# plaits_v50.net
KiCad netlist of a schematic drawn in EAGLE
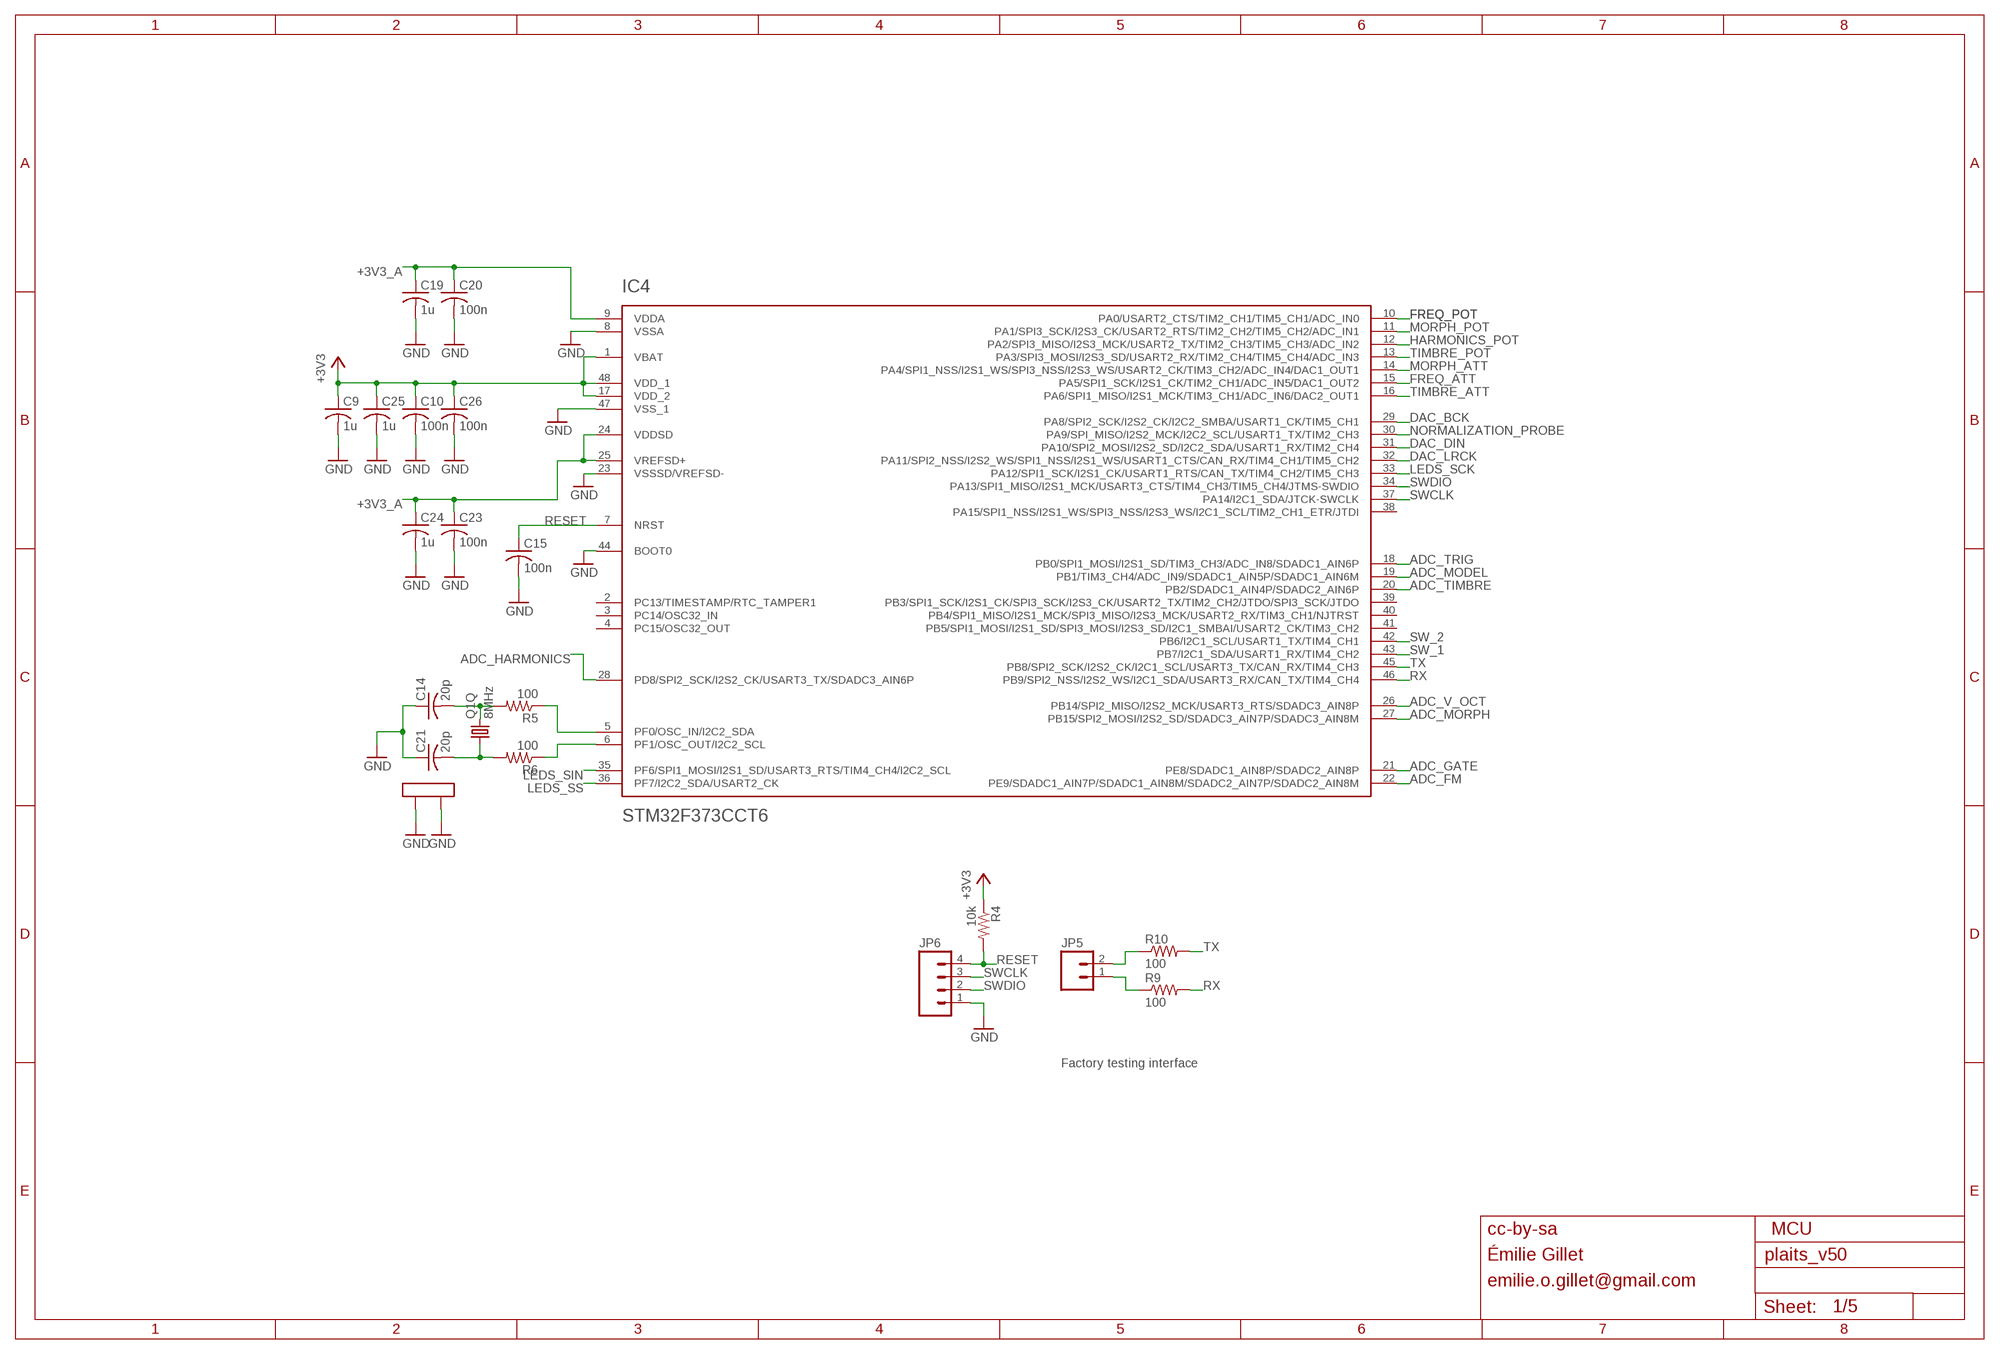
[diagram p0: schematic, sheet 1]
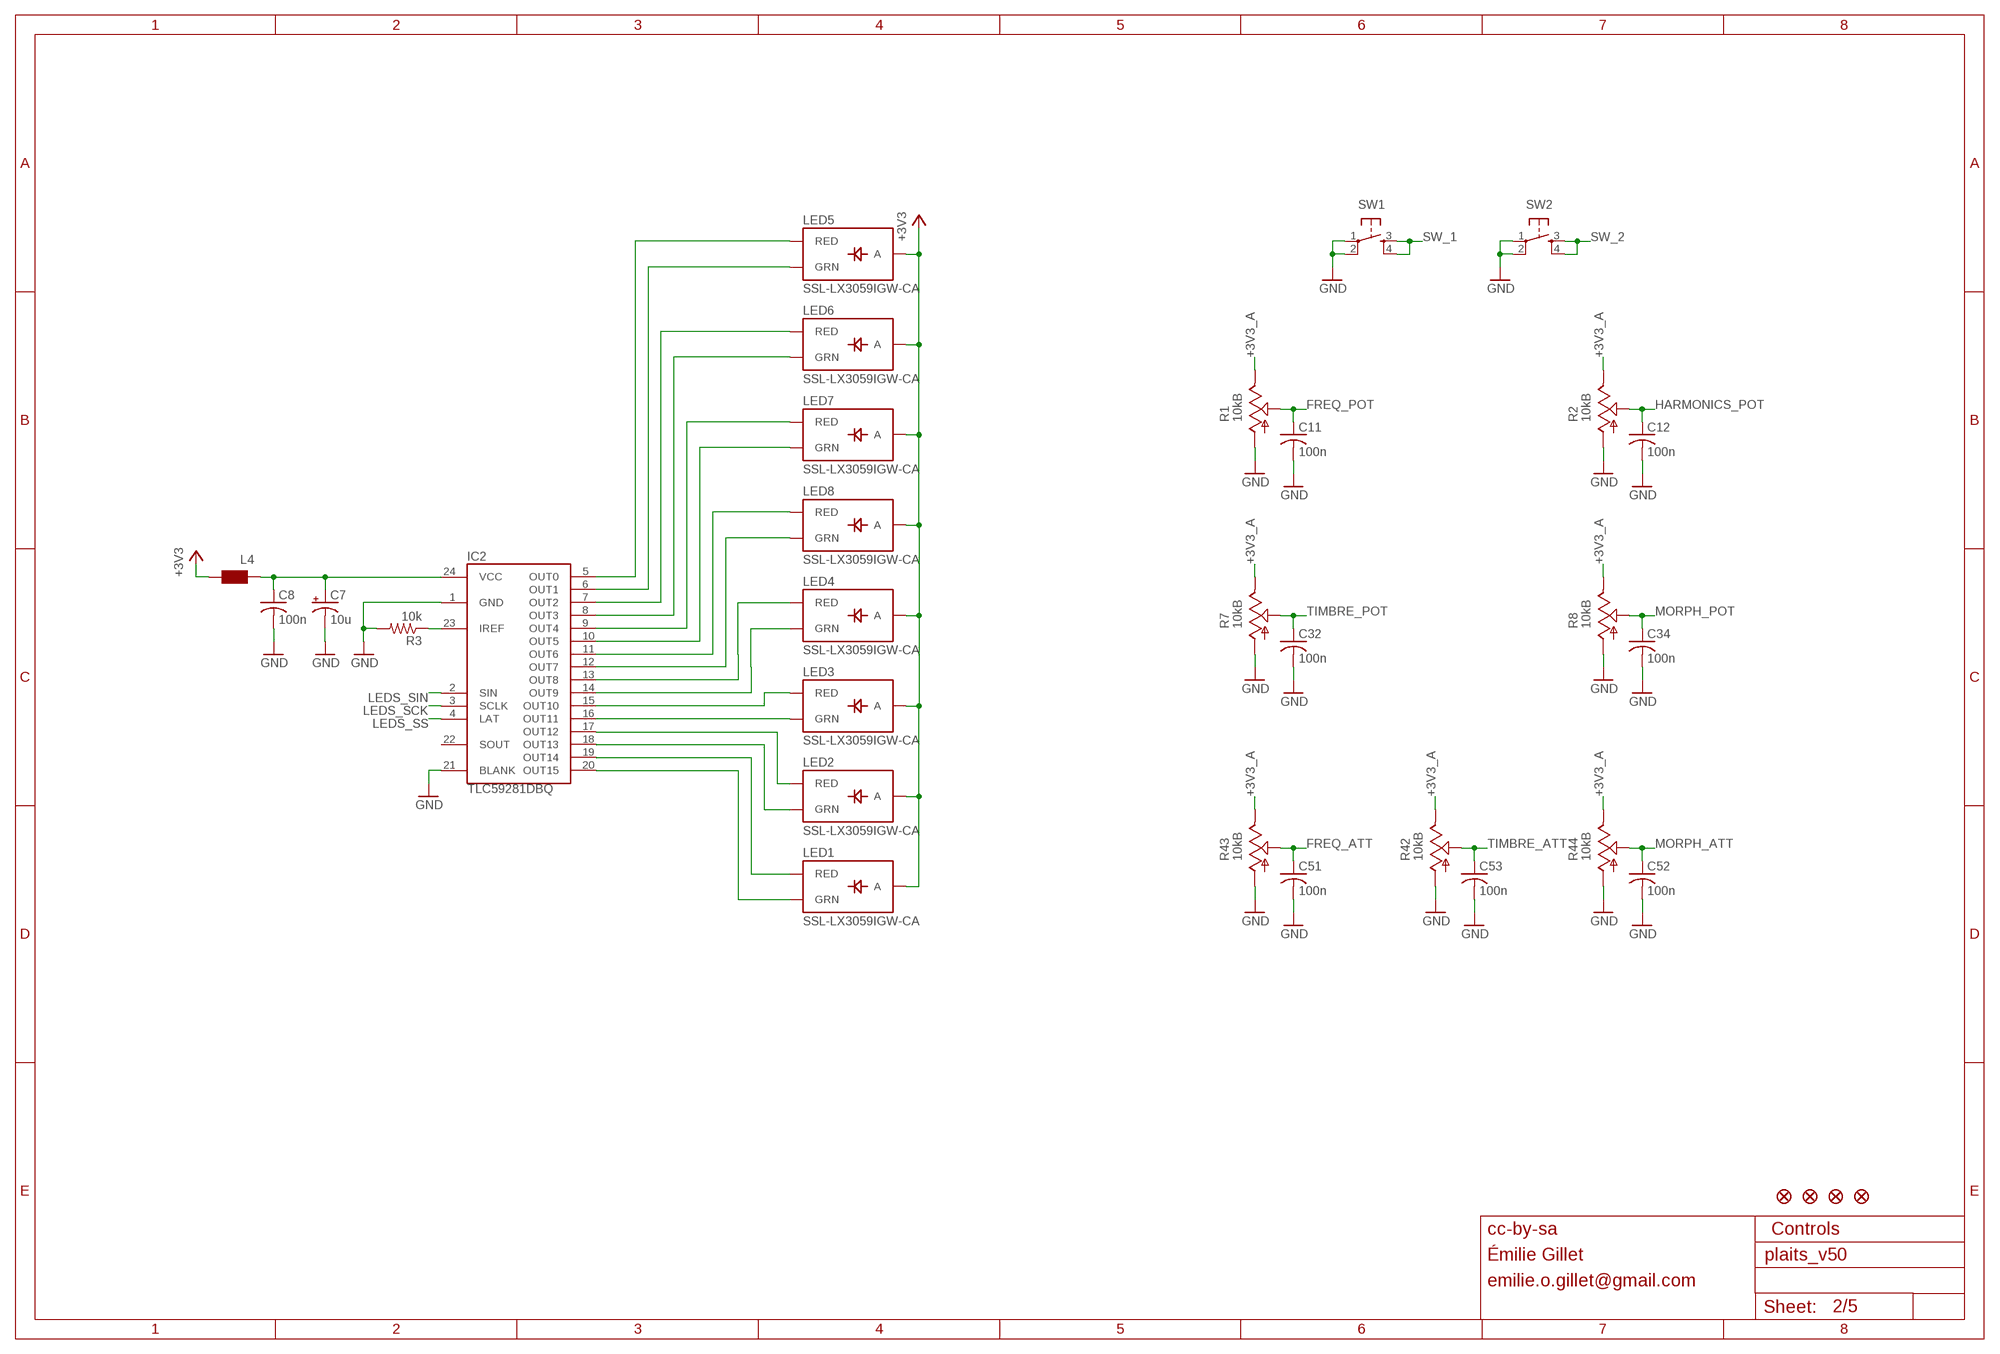
[diagram p1: schematic, sheet 2]
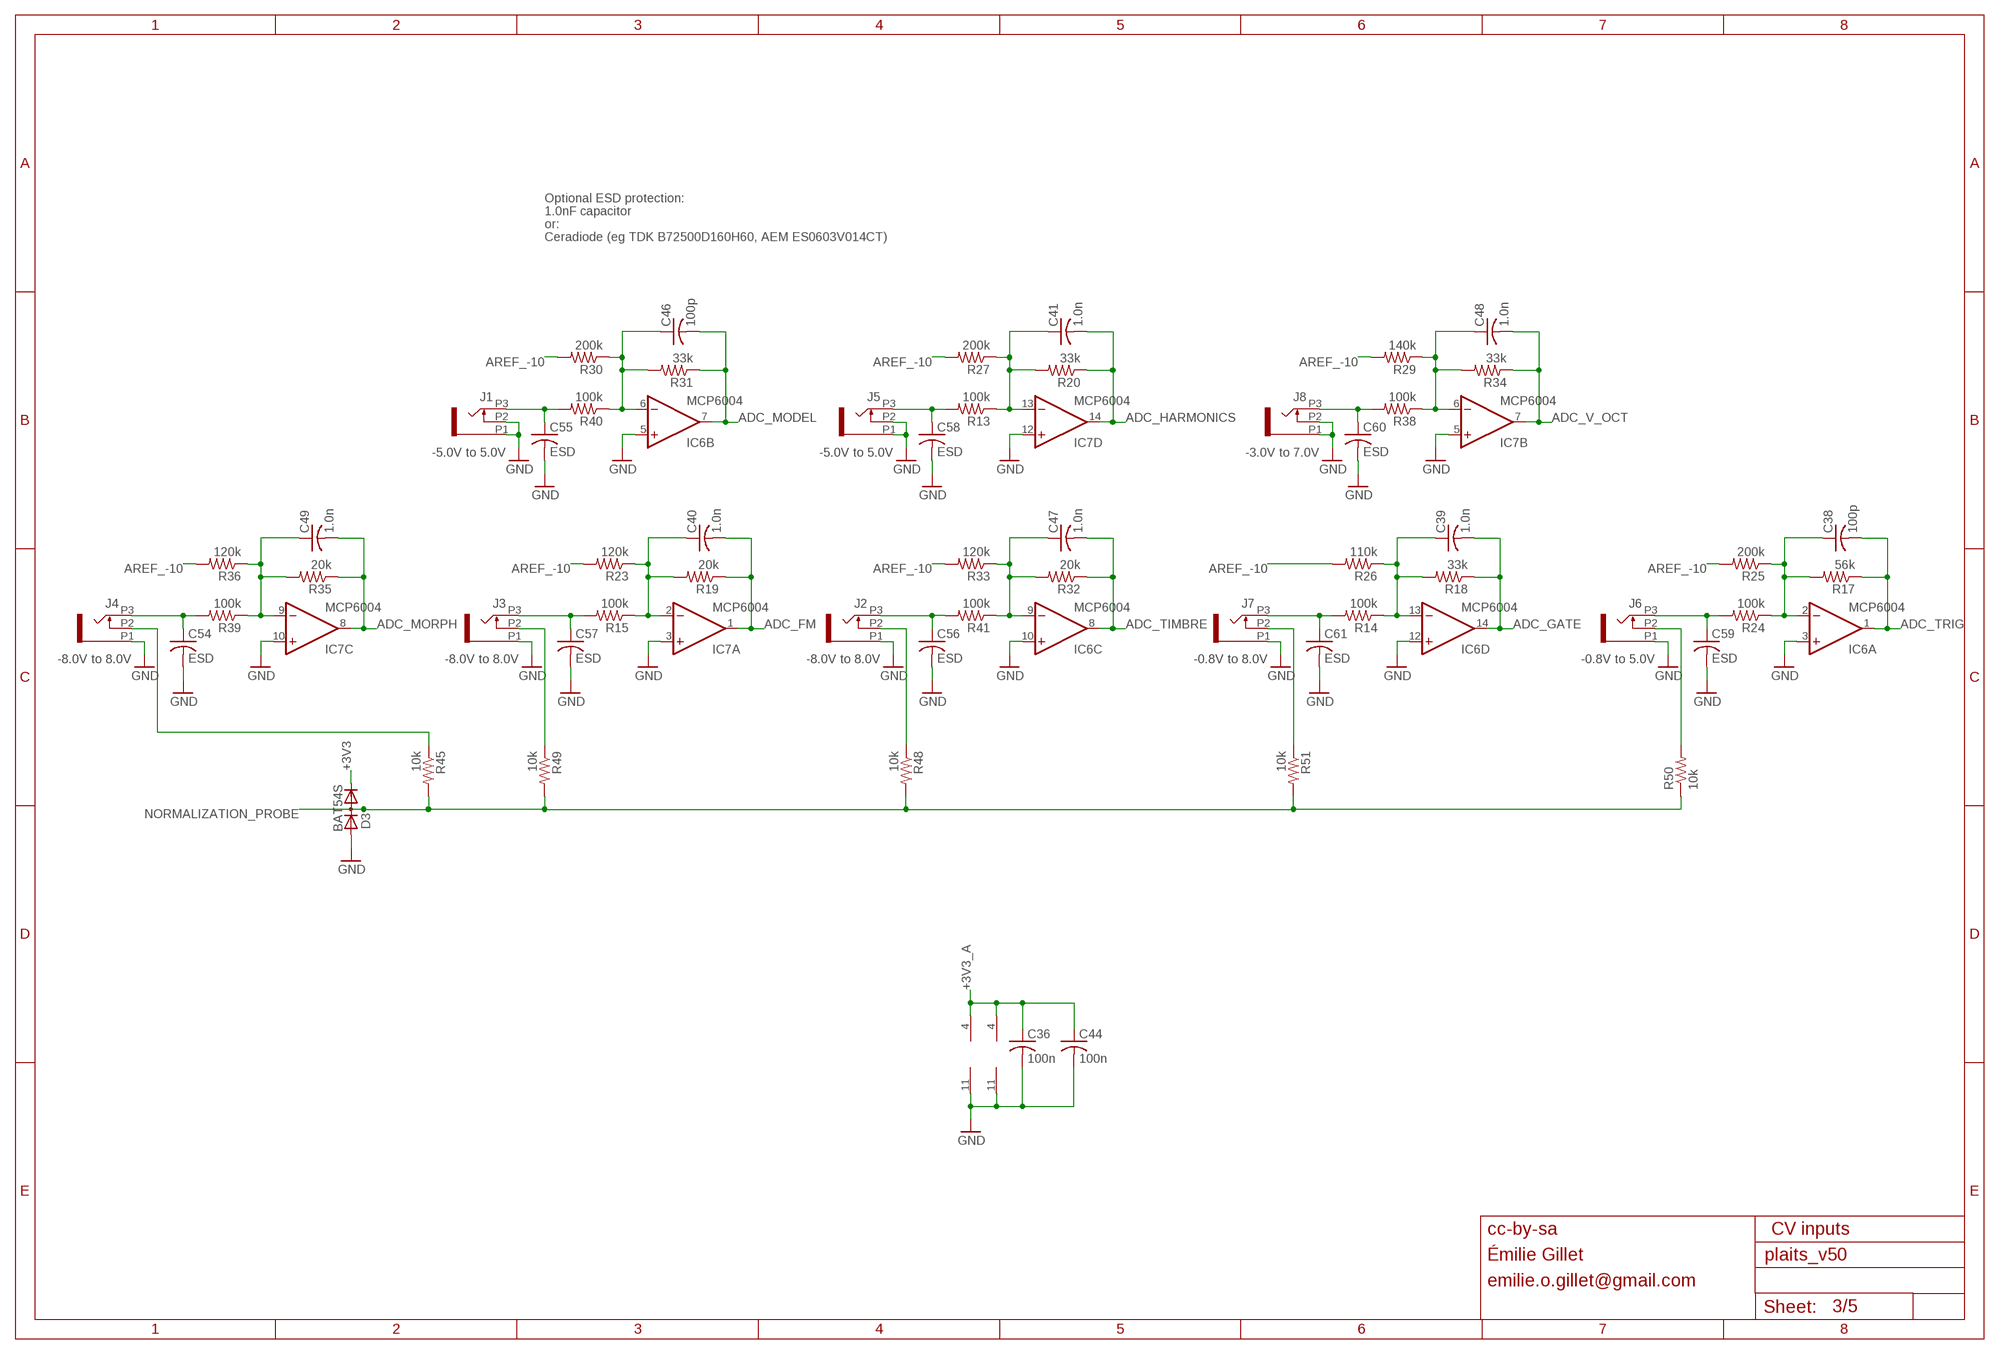
[diagram p2: schematic, sheet 3]
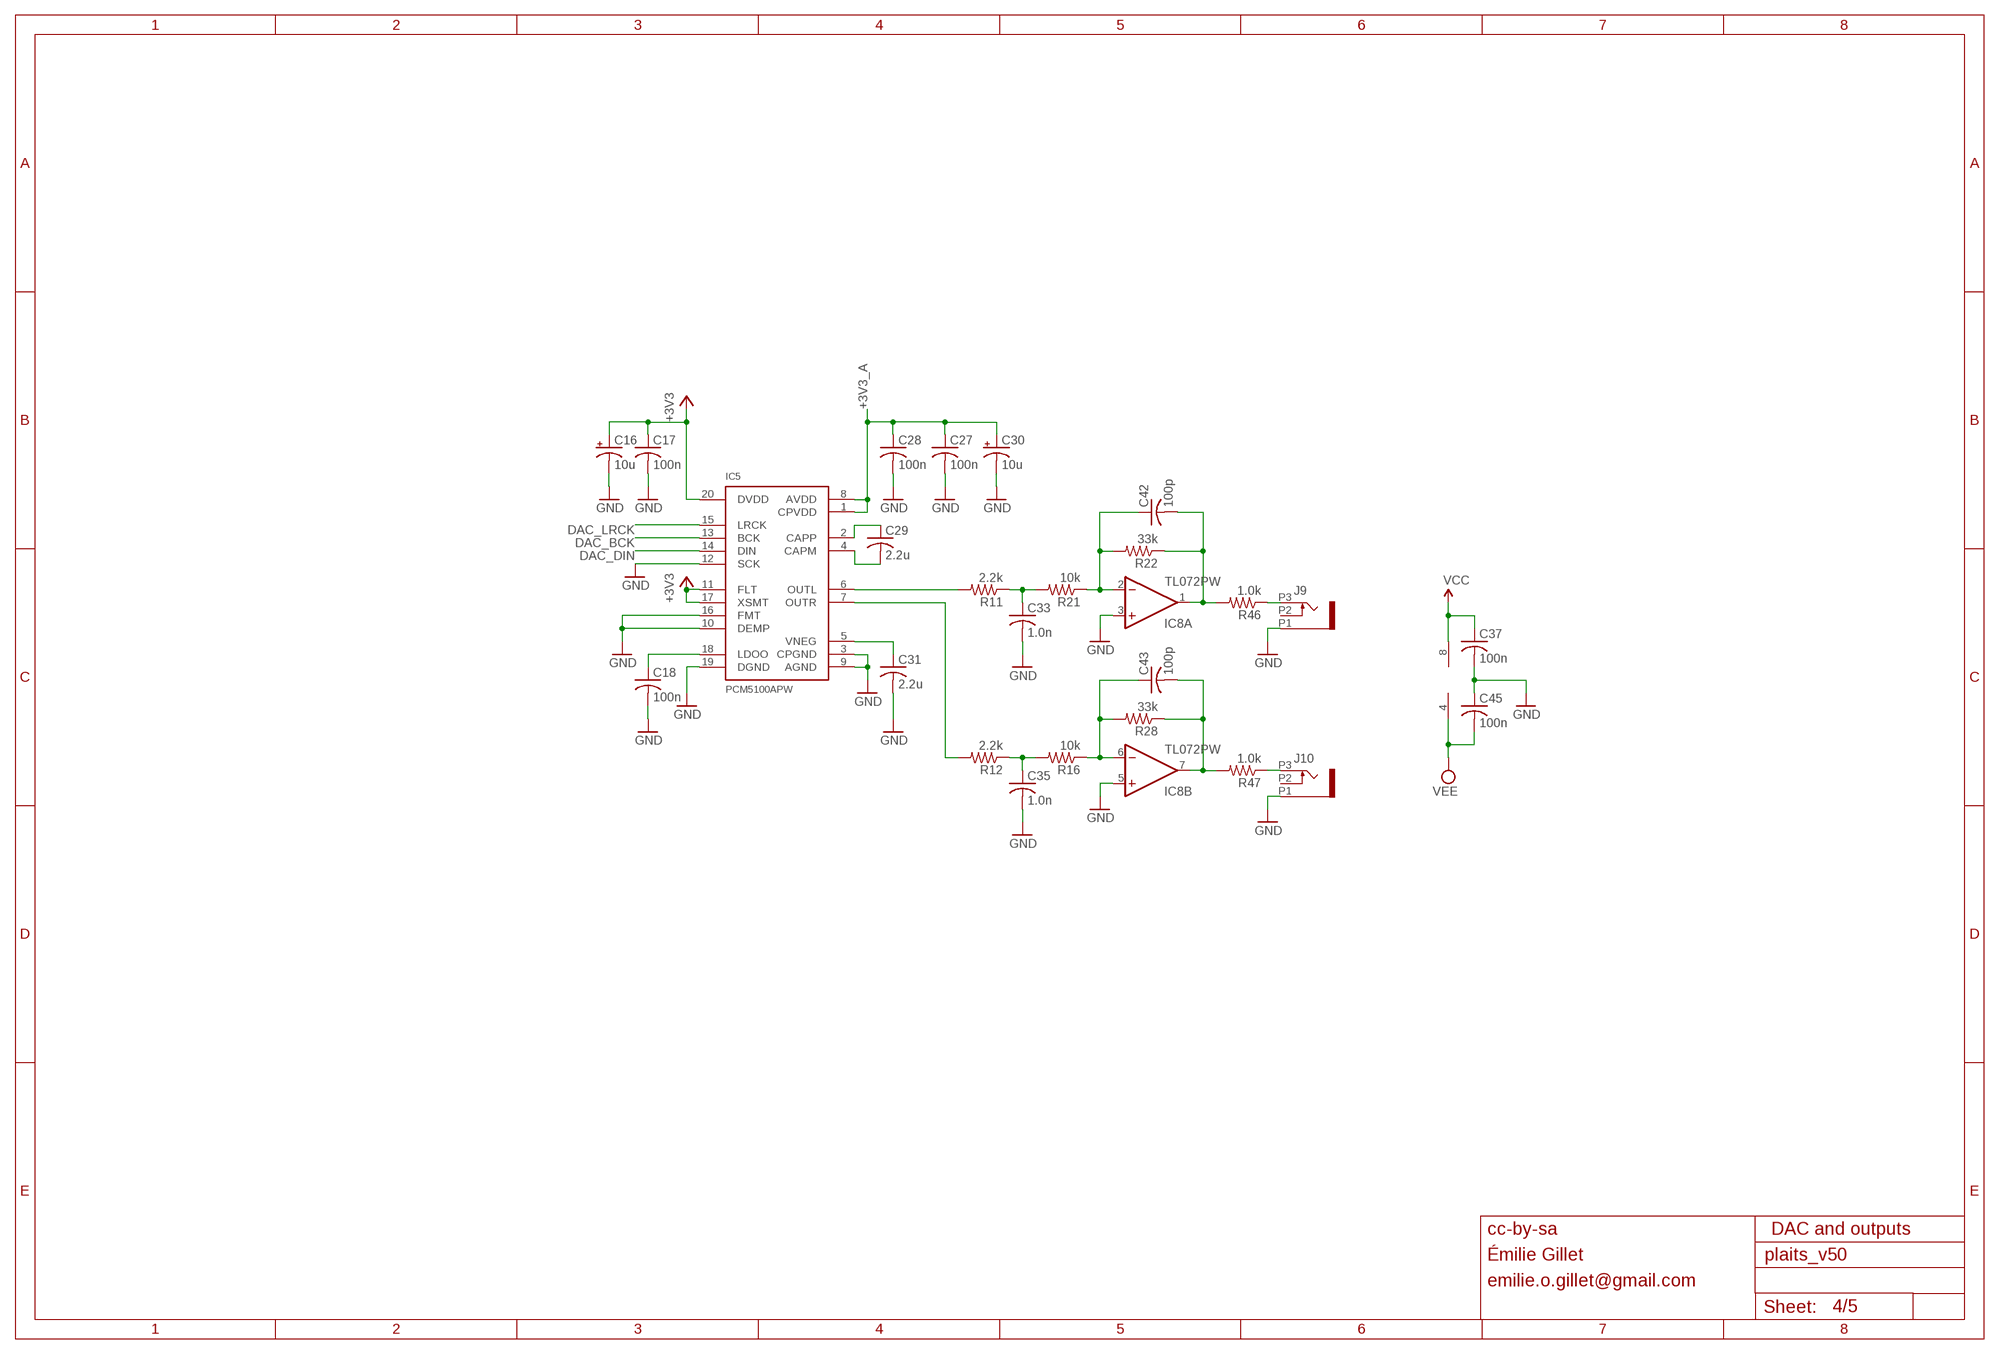
[diagram p3: schematic, sheet 4]
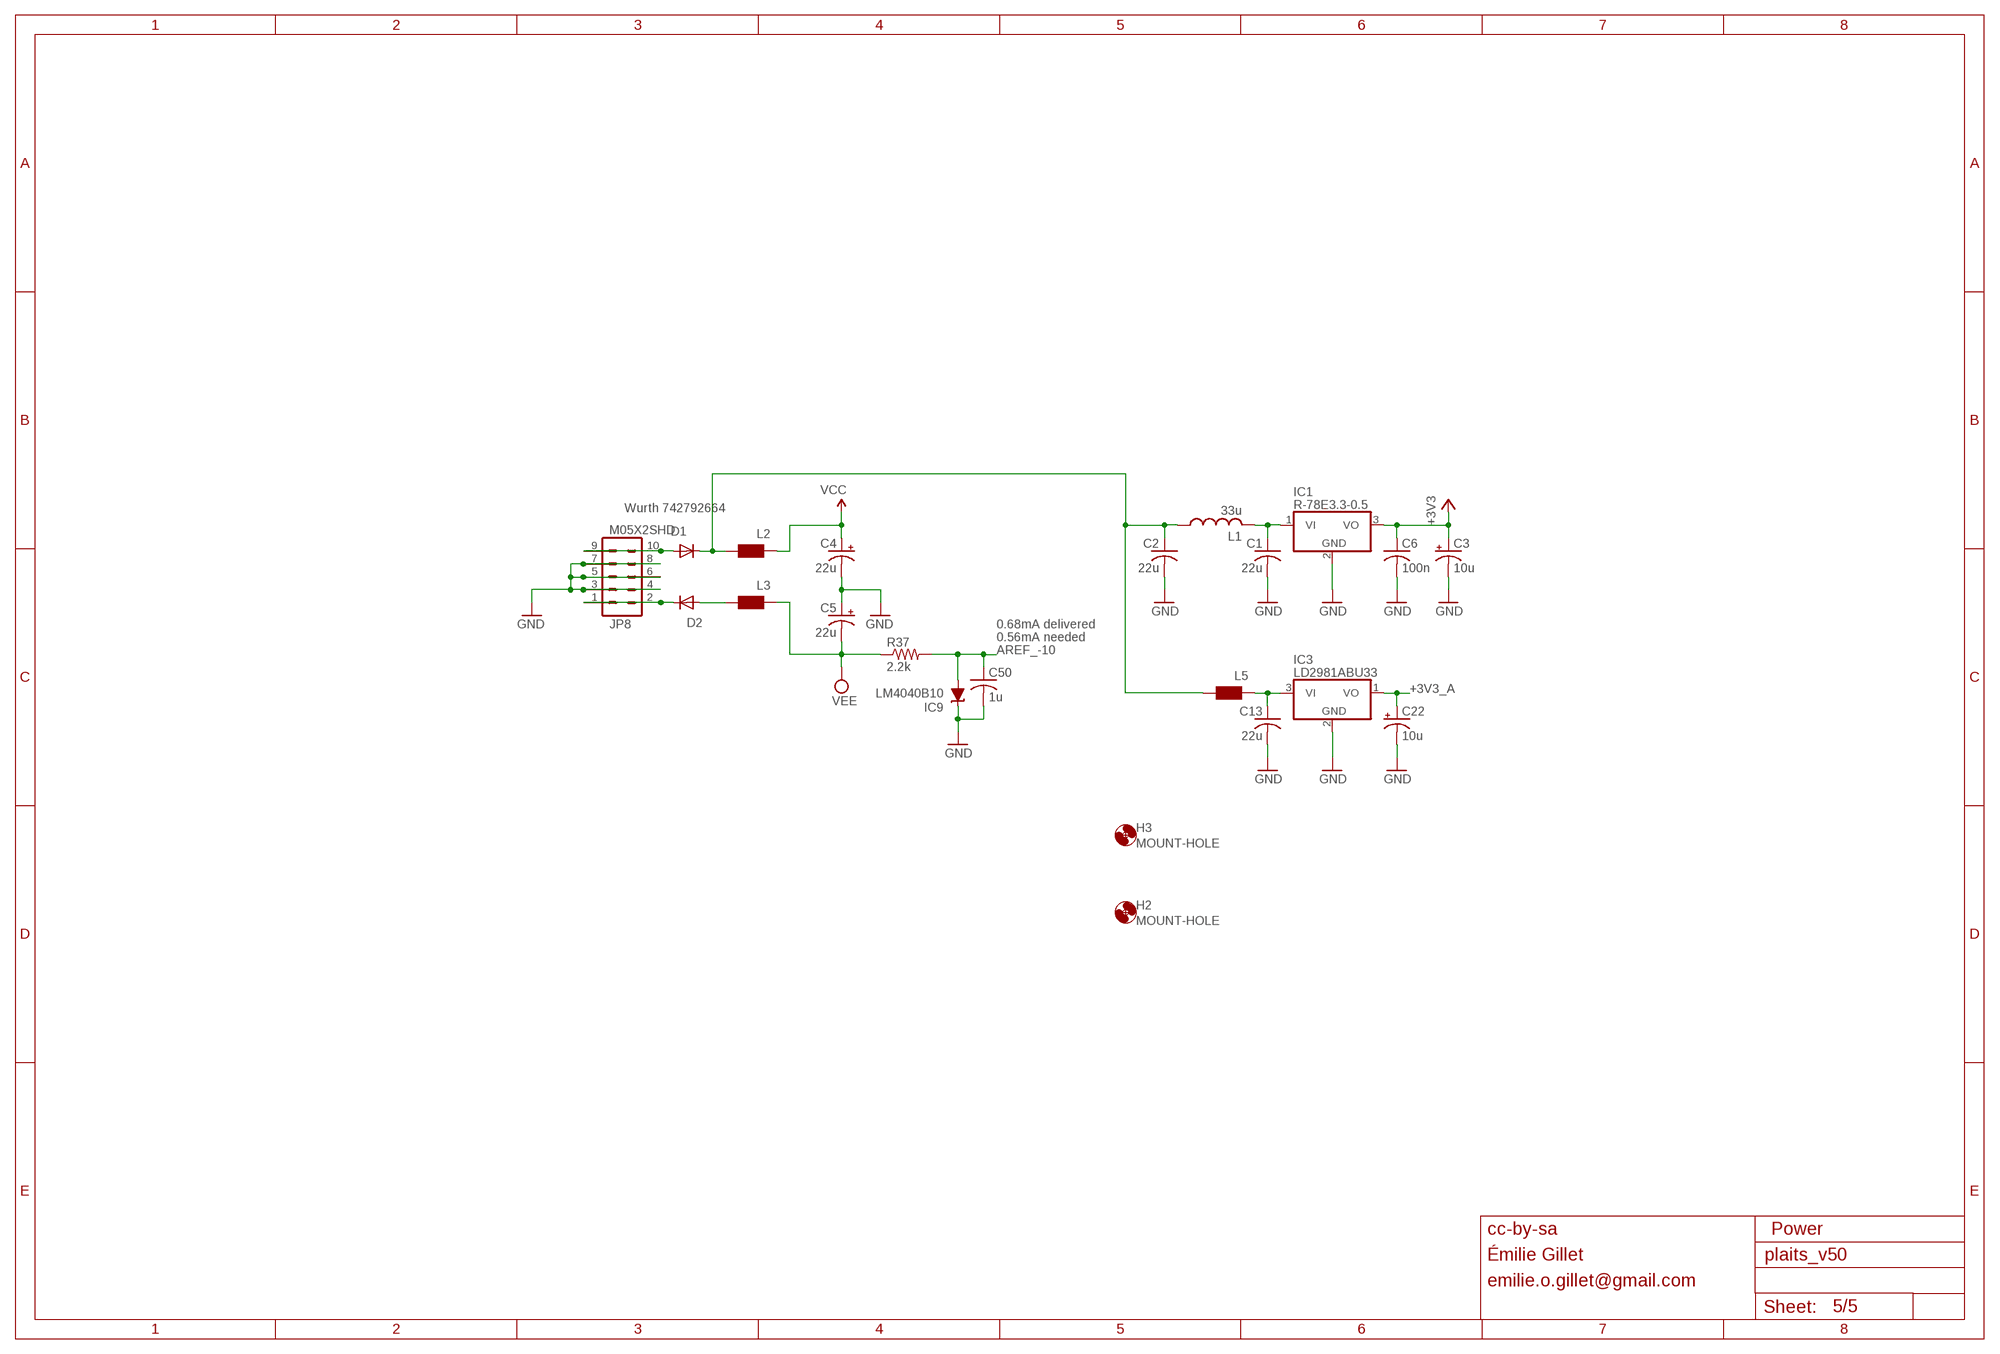
[diagram p4: schematic, sheet 5]

(export (version "E")
  (design (tool "Eeschema 10.0.6"))
  (components
    (comp (ref "C7")
      (value "10u")
      (footprint "eagle-import:PANASONIC_A")
      (libsource (lib "eagle-import") (part "CPOL-USA"))
    )
    (comp (ref "C8")
      (value "100n")
      (footprint "eagle-import:C0402")
      (libsource (lib "eagle-import") (part "C-USC0402"))
    )
    (comp (ref "C11")
      (value "100n")
      (footprint "eagle-import:C0402")
      (libsource (lib "eagle-import") (part "C-USC0402"))
    )
    (comp (ref "C12")
      (value "100n")
      (footprint "eagle-import:C0402")
      (libsource (lib "eagle-import") (part "C-USC0402"))
    )
    (comp (ref "C32")
      (value "100n")
      (footprint "eagle-import:C0402")
      (libsource (lib "eagle-import") (part "C-USC0402"))
    )
    (comp (ref "C34")
      (value "100n")
      (footprint "eagle-import:C0402")
      (libsource (lib "eagle-import") (part "C-USC0402"))
    )
    (comp (ref "C51")
      (value "100n")
      (footprint "eagle-import:C0402")
      (libsource (lib "eagle-import") (part "C-USC0402"))
    )
    (comp (ref "C52")
      (value "100n")
      (footprint "eagle-import:C0402")
      (libsource (lib "eagle-import") (part "C-USC0402"))
    )
    (comp (ref "C53")
      (value "100n")
      (footprint "eagle-import:C0402")
      (libsource (lib "eagle-import") (part "C-USC0402"))
    )
    (comp (ref "IC2")
      (value "TLC59281DBQ")
      (footprint "eagle-import:TSSOP24_0635")
      (libsource (lib "eagle-import") (part "TLC59281DBQ"))
    )
    (comp (ref "JP1")
      (value "FIDUCIAL1X2")
      (footprint "eagle-import:FIDUCIAL-1X2")
      (libsource (lib "eagle-import") (part "FIDUCIAL1X2"))
    )
    (comp (ref "JP2")
      (value "FIDUCIAL1X2")
      (footprint "eagle-import:FIDUCIAL-1X2")
      (libsource (lib "eagle-import") (part "FIDUCIAL1X2"))
    )
    (comp (ref "JP3")
      (value "FIDUCIAL1X2")
      (footprint "eagle-import:FIDUCIAL-1X2")
      (libsource (lib "eagle-import") (part "FIDUCIAL1X2"))
    )
    (comp (ref "JP4")
      (value "FIDUCIAL1X2")
      (footprint "eagle-import:FIDUCIAL-1X2")
      (libsource (lib "eagle-import") (part "FIDUCIAL1X2"))
    )
    (comp (ref "L4")
      (value "WE-CBF_0603")
      (footprint "eagle-import:0603")
      (libsource (lib "eagle-import") (part "WE-CBF_0603"))
    )
    (comp (ref "LED1")
      (value "SSL-LX3059IGW-CA")
      (footprint "eagle-import:LED-BICOLOR-THROUGHHOLE-LUMEX")
      (libsource (lib "eagle-import") (part "LED-BICOLOR-THROUGHHOLE-CA"))
    )
    (comp (ref "LED2")
      (value "SSL-LX3059IGW-CA")
      (footprint "eagle-import:LED-BICOLOR-THROUGHHOLE-LUMEX")
      (libsource (lib "eagle-import") (part "LED-BICOLOR-THROUGHHOLE-CA"))
    )
    (comp (ref "LED3")
      (value "SSL-LX3059IGW-CA")
      (footprint "eagle-import:LED-BICOLOR-THROUGHHOLE-LUMEX")
      (libsource (lib "eagle-import") (part "LED-BICOLOR-THROUGHHOLE-CA"))
    )
    (comp (ref "LED4")
      (value "SSL-LX3059IGW-CA")
      (footprint "eagle-import:LED-BICOLOR-THROUGHHOLE-LUMEX")
      (libsource (lib "eagle-import") (part "LED-BICOLOR-THROUGHHOLE-CA"))
    )
    (comp (ref "LED5")
      (value "SSL-LX3059IGW-CA")
      (footprint "eagle-import:LED-BICOLOR-THROUGHHOLE-LUMEX")
      (libsource (lib "eagle-import") (part "LED-BICOLOR-THROUGHHOLE-CA"))
    )
    (comp (ref "LED6")
      (value "SSL-LX3059IGW-CA")
      (footprint "eagle-import:LED-BICOLOR-THROUGHHOLE-LUMEX")
      (libsource (lib "eagle-import") (part "LED-BICOLOR-THROUGHHOLE-CA"))
    )
    (comp (ref "LED7")
      (value "SSL-LX3059IGW-CA")
      (footprint "eagle-import:LED-BICOLOR-THROUGHHOLE-LUMEX")
      (libsource (lib "eagle-import") (part "LED-BICOLOR-THROUGHHOLE-CA"))
    )
    (comp (ref "LED8")
      (value "SSL-LX3059IGW-CA")
      (footprint "eagle-import:LED-BICOLOR-THROUGHHOLE-LUMEX")
      (libsource (lib "eagle-import") (part "LED-BICOLOR-THROUGHHOLE-CA"))
    )
    (comp (ref "R1")
      (value "10kB")
      (footprint "eagle-import:ALPS_POT_VERTICAL_PS")
      (libsource (lib "eagle-import") (part "POT_USVERTICAL_PS"))
    )
    (comp (ref "R2")
      (value "10kB")
      (footprint "eagle-import:ALPS_POT_VERTICAL_PS")
      (libsource (lib "eagle-import") (part "POT_USVERTICAL_PS"))
    )
    (comp (ref "R3")
      (value "10k")
      (footprint "eagle-import:R0402")
      (libsource (lib "eagle-import") (part "R-US_R0402"))
    )
    (comp (ref "R7")
      (value "10kB")
      (footprint "eagle-import:ALPS_POT_VERTICAL_PS")
      (libsource (lib "eagle-import") (part "POT_USVERTICAL_PS"))
    )
    (comp (ref "R8")
      (value "10kB")
      (footprint "eagle-import:ALPS_POT_VERTICAL_PS")
      (libsource (lib "eagle-import") (part "POT_USVERTICAL_PS"))
    )
    (comp (ref "R42")
      (value "10kB")
      (footprint "eagle-import:ALPS_POT_VERTICAL")
      (libsource (lib "eagle-import") (part "POT_USVERTICAL"))
    )
    (comp (ref "R43")
      (value "10kB")
      (footprint "eagle-import:ALPS_POT_VERTICAL")
      (libsource (lib "eagle-import") (part "POT_USVERTICAL"))
    )
    (comp (ref "R44")
      (value "10kB")
      (footprint "eagle-import:ALPS_POT_VERTICAL")
      (libsource (lib "eagle-import") (part "POT_USVERTICAL"))
    )
    (comp (ref "SW1")
      (value "TAC_SWITCHPTH")
      (footprint "eagle-import:TACTILE-PTH")
      (libsource (lib "eagle-import") (part "TAC_SWITCHPTH"))
    )
    (comp (ref "SW2")
      (value "TAC_SWITCHPTH")
      (footprint "eagle-import:TACTILE-PTH")
      (libsource (lib "eagle-import") (part "TAC_SWITCHPTH"))
    )
    (comp (ref "C36")
      (value "100n")
      (footprint "eagle-import:C0402")
      (libsource (lib "eagle-import") (part "C-USC0402"))
    )
    (comp (ref "C38")
      (value "100p")
      (footprint "eagle-import:C0402")
      (libsource (lib "eagle-import") (part "C-USC0402"))
    )
    (comp (ref "C39")
      (value "1.0n")
      (footprint "eagle-import:C0402")
      (libsource (lib "eagle-import") (part "C-USC0402"))
    )
    (comp (ref "C40")
      (value "1.0n")
      (footprint "eagle-import:C0402")
      (libsource (lib "eagle-import") (part "C-USC0402"))
    )
    (comp (ref "C41")
      (value "1.0n")
      (footprint "eagle-import:C0402")
      (libsource (lib "eagle-import") (part "C-USC0402"))
    )
    (comp (ref "C44")
      (value "100n")
      (footprint "eagle-import:C0402")
      (libsource (lib "eagle-import") (part "C-USC0402"))
    )
    (comp (ref "C46")
      (value "100p")
      (footprint "eagle-import:C0402")
      (libsource (lib "eagle-import") (part "C-USC0402"))
    )
    (comp (ref "C47")
      (value "1.0n")
      (footprint "eagle-import:C0402")
      (libsource (lib "eagle-import") (part "C-USC0402"))
    )
    (comp (ref "C48")
      (value "1.0n")
      (footprint "eagle-import:C0402")
      (libsource (lib "eagle-import") (part "C-USC0402"))
    )
    (comp (ref "C49")
      (value "1.0n")
      (footprint "eagle-import:C0402")
      (libsource (lib "eagle-import") (part "C-USC0402"))
    )
    (comp (ref "C54")
      (value "ESD")
      (footprint "eagle-import:C0603")
      (libsource (lib "eagle-import") (part "C-USC0603"))
    )
    (comp (ref "C55")
      (value "ESD")
      (footprint "eagle-import:C0603")
      (libsource (lib "eagle-import") (part "C-USC0603"))
    )
    (comp (ref "C56")
      (value "ESD")
      (footprint "eagle-import:C0603")
      (libsource (lib "eagle-import") (part "C-USC0603"))
    )
    (comp (ref "C57")
      (value "ESD")
      (footprint "eagle-import:C0603")
      (libsource (lib "eagle-import") (part "C-USC0603"))
    )
    (comp (ref "C58")
      (value "ESD")
      (footprint "eagle-import:C0603")
      (libsource (lib "eagle-import") (part "C-USC0603"))
    )
    (comp (ref "C59")
      (value "ESD")
      (footprint "eagle-import:C0603")
      (libsource (lib "eagle-import") (part "C-USC0603"))
    )
    (comp (ref "C60")
      (value "ESD")
      (footprint "eagle-import:C0603")
      (libsource (lib "eagle-import") (part "C-USC0603"))
    )
    (comp (ref "C61")
      (value "ESD")
      (footprint "eagle-import:C0603")
      (libsource (lib "eagle-import") (part "C-USC0603"))
    )
    (comp (ref "D3")
      (value "BAT54S")
      (footprint "eagle-import:SOT23")
      (libsource (lib "eagle-import") (part "DIODE_2CACA-SOT23"))
    )
    (comp (ref "IC6")
      (value "MCP6004")
      (footprint "eagle-import:TSSOP14_065")
      (libsource (lib "eagle-import") (part "TL074PW"))
    )
    (comp (ref "IC7")
      (value "MCP6004")
      (footprint "eagle-import:TSSOP14_065")
      (libsource (lib "eagle-import") (part "TL074PW"))
    )
    (comp (ref "J1")
      (value "PJ301_THONKICONN6")
      (footprint "eagle-import:WQP_PJ_301M6")
      (libsource (lib "eagle-import") (part "PJ301_THONKICONN6"))
    )
    (comp (ref "J2")
      (value "PJ301_THONKICONN6")
      (footprint "eagle-import:WQP_PJ_301M6")
      (libsource (lib "eagle-import") (part "PJ301_THONKICONN6"))
    )
    (comp (ref "J3")
      (value "PJ301_THONKICONN6")
      (footprint "eagle-import:WQP_PJ_301M6")
      (libsource (lib "eagle-import") (part "PJ301_THONKICONN6"))
    )
    (comp (ref "J4")
      (value "PJ301_THONKICONN6")
      (footprint "eagle-import:WQP_PJ_301M6")
      (libsource (lib "eagle-import") (part "PJ301_THONKICONN6"))
    )
    (comp (ref "J5")
      (value "PJ301_THONKICONN6")
      (footprint "eagle-import:WQP_PJ_301M6")
      (libsource (lib "eagle-import") (part "PJ301_THONKICONN6"))
    )
    (comp (ref "J6")
      (value "PJ301_THONKICONN6")
      (footprint "eagle-import:WQP_PJ_301M6")
      (libsource (lib "eagle-import") (part "PJ301_THONKICONN6"))
    )
    (comp (ref "J7")
      (value "PJ301_THONKICONN6")
      (footprint "eagle-import:WQP_PJ_301M6")
      (libsource (lib "eagle-import") (part "PJ301_THONKICONN6"))
    )
    (comp (ref "J8")
      (value "PJ301_THONKICONN6")
      (footprint "eagle-import:WQP_PJ_301M6")
      (libsource (lib "eagle-import") (part "PJ301_THONKICONN6"))
    )
    (comp (ref "R13")
      (value "100k")
      (footprint "eagle-import:R0402")
      (libsource (lib "eagle-import") (part "R-US_R0402"))
    )
    (comp (ref "R14")
      (value "100k")
      (footprint "eagle-import:R0402")
      (libsource (lib "eagle-import") (part "R-US_R0402"))
    )
    (comp (ref "R15")
      (value "100k")
      (footprint "eagle-import:R0402")
      (libsource (lib "eagle-import") (part "R-US_R0402"))
    )
    (comp (ref "R17")
      (value "56k")
      (footprint "eagle-import:R0402")
      (libsource (lib "eagle-import") (part "R-US_R0402"))
    )
    (comp (ref "R18")
      (value "33k")
      (footprint "eagle-import:R0402")
      (libsource (lib "eagle-import") (part "R-US_R0402"))
    )
    (comp (ref "R19")
      (value "20k")
      (footprint "eagle-import:R0402")
      (libsource (lib "eagle-import") (part "R-US_R0402"))
    )
    (comp (ref "R20")
      (value "33k")
      (footprint "eagle-import:R0402")
      (libsource (lib "eagle-import") (part "R-US_R0402"))
    )
    (comp (ref "R23")
      (value "120k")
      (footprint "eagle-import:R0402")
      (libsource (lib "eagle-import") (part "R-US_R0402"))
    )
    (comp (ref "R24")
      (value "100k")
      (footprint "eagle-import:R0402")
      (libsource (lib "eagle-import") (part "R-US_R0402"))
    )
    (comp (ref "R25")
      (value "200k")
      (footprint "eagle-import:R0402")
      (libsource (lib "eagle-import") (part "R-US_R0402"))
    )
    (comp (ref "R26")
      (value "110k")
      (footprint "eagle-import:R0402")
      (libsource (lib "eagle-import") (part "R-US_R0402"))
    )
    (comp (ref "R27")
      (value "200k")
      (footprint "eagle-import:R0402")
      (libsource (lib "eagle-import") (part "R-US_R0402"))
    )
    (comp (ref "R29")
      (value "140k")
      (footprint "eagle-import:R0402")
      (libsource (lib "eagle-import") (part "R-US_R0402"))
    )
    (comp (ref "R30")
      (value "200k")
      (footprint "eagle-import:R0402")
      (libsource (lib "eagle-import") (part "R-US_R0402"))
    )
    (comp (ref "R31")
      (value "33k")
      (footprint "eagle-import:R0402")
      (libsource (lib "eagle-import") (part "R-US_R0402"))
    )
    (comp (ref "R32")
      (value "20k")
      (footprint "eagle-import:R0402")
      (libsource (lib "eagle-import") (part "R-US_R0402"))
    )
    (comp (ref "R33")
      (value "120k")
      (footprint "eagle-import:R0402")
      (libsource (lib "eagle-import") (part "R-US_R0402"))
    )
    (comp (ref "R34")
      (value "33k")
      (footprint "eagle-import:R0402")
      (libsource (lib "eagle-import") (part "R-US_R0402"))
    )
    (comp (ref "R35")
      (value "20k")
      (footprint "eagle-import:R0402")
      (libsource (lib "eagle-import") (part "R-US_R0402"))
    )
    (comp (ref "R36")
      (value "120k")
      (footprint "eagle-import:R0402")
      (libsource (lib "eagle-import") (part "R-US_R0402"))
    )
    (comp (ref "R38")
      (value "100k")
      (footprint "eagle-import:R0402")
      (libsource (lib "eagle-import") (part "R-US_R0402"))
    )
    (comp (ref "R39")
      (value "100k")
      (footprint "eagle-import:R0402")
      (libsource (lib "eagle-import") (part "R-US_R0402"))
    )
    (comp (ref "R40")
      (value "100k")
      (footprint "eagle-import:R0402")
      (libsource (lib "eagle-import") (part "R-US_R0402"))
    )
    (comp (ref "R41")
      (value "100k")
      (footprint "eagle-import:R0402")
      (libsource (lib "eagle-import") (part "R-US_R0402"))
    )
    (comp (ref "R45")
      (value "10k")
      (footprint "eagle-import:R0402")
      (libsource (lib "eagle-import") (part "R-US_R0402"))
    )
    (comp (ref "R48")
      (value "10k")
      (footprint "eagle-import:R0402")
      (libsource (lib "eagle-import") (part "R-US_R0402"))
    )
    (comp (ref "R49")
      (value "10k")
      (footprint "eagle-import:R0402")
      (libsource (lib "eagle-import") (part "R-US_R0402"))
    )
    (comp (ref "R50")
      (value "10k")
      (footprint "eagle-import:R0402")
      (libsource (lib "eagle-import") (part "R-US_R0402"))
    )
    (comp (ref "R51")
      (value "10k")
      (footprint "eagle-import:R0402")
      (libsource (lib "eagle-import") (part "R-US_R0402"))
    )
    (comp (ref "C16")
      (value "10u")
      (footprint "eagle-import:PANASONIC_A")
      (libsource (lib "eagle-import") (part "CPOL-USA"))
    )
    (comp (ref "C17")
      (value "100n")
      (footprint "eagle-import:C0402")
      (libsource (lib "eagle-import") (part "C-USC0402"))
    )
    (comp (ref "C18")
      (value "100n")
      (footprint "eagle-import:C0402")
      (libsource (lib "eagle-import") (part "C-USC0402"))
    )
    (comp (ref "C27")
      (value "100n")
      (footprint "eagle-import:C0402")
      (libsource (lib "eagle-import") (part "C-USC0402"))
    )
    (comp (ref "C28")
      (value "100n")
      (footprint "eagle-import:C0402")
      (libsource (lib "eagle-import") (part "C-USC0402"))
    )
    (comp (ref "C29")
      (value "2.2u")
      (footprint "eagle-import:C0805")
      (libsource (lib "eagle-import") (part "C-USC0805"))
    )
    (comp (ref "C30")
      (value "10u")
      (footprint "eagle-import:PANASONIC_A")
      (libsource (lib "eagle-import") (part "CPOL-USA"))
    )
    (comp (ref "C31")
      (value "2.2u")
      (footprint "eagle-import:C0805")
      (libsource (lib "eagle-import") (part "C-USC0805"))
    )
    (comp (ref "C33")
      (value "1.0n")
      (footprint "eagle-import:C0402")
      (libsource (lib "eagle-import") (part "C-USC0402"))
    )
    (comp (ref "C35")
      (value "1.0n")
      (footprint "eagle-import:C0402")
      (libsource (lib "eagle-import") (part "C-USC0402"))
    )
    (comp (ref "C37")
      (value "100n")
      (footprint "eagle-import:C0402")
      (libsource (lib "eagle-import") (part "C-USC0402"))
    )
    (comp (ref "C42")
      (value "100p")
      (footprint "eagle-import:C0402")
      (libsource (lib "eagle-import") (part "C-USC0402"))
    )
    (comp (ref "C43")
      (value "100p")
      (footprint "eagle-import:C0402")
      (libsource (lib "eagle-import") (part "C-USC0402"))
    )
    (comp (ref "C45")
      (value "100n")
      (footprint "eagle-import:C0402")
      (libsource (lib "eagle-import") (part "C-USC0402"))
    )
    (comp (ref "IC5")
      (value "PCM5100APW")
      (footprint "eagle-import:SSOP20")
      (libsource (lib "eagle-import") (part "PCM5100PW"))
    )
    (comp (ref "IC8")
      (value "TL072PW")
      (footprint "eagle-import:TSSOP08")
      (libsource (lib "eagle-import") (part "TL072PW"))
    )
    (comp (ref "J9")
      (value "PJ301_THONKICONN6")
      (footprint "eagle-import:WQP_PJ_301M6")
      (libsource (lib "eagle-import") (part "PJ301_THONKICONN6"))
    )
    (comp (ref "J10")
      (value "PJ301_THONKICONN6")
      (footprint "eagle-import:WQP_PJ_301M6")
      (libsource (lib "eagle-import") (part "PJ301_THONKICONN6"))
    )
    (comp (ref "R11")
      (value "2.2k")
      (footprint "eagle-import:R0402")
      (libsource (lib "eagle-import") (part "R-US_R0402"))
    )
    (comp (ref "R12")
      (value "2.2k")
      (footprint "eagle-import:R0402")
      (libsource (lib "eagle-import") (part "R-US_R0402"))
    )
    (comp (ref "R16")
      (value "10k")
      (footprint "eagle-import:R0402")
      (libsource (lib "eagle-import") (part "R-US_R0402"))
    )
    (comp (ref "R21")
      (value "10k")
      (footprint "eagle-import:R0402")
      (libsource (lib "eagle-import") (part "R-US_R0402"))
    )
    (comp (ref "R22")
      (value "33k")
      (footprint "eagle-import:R0402")
      (libsource (lib "eagle-import") (part "R-US_R0402"))
    )
    (comp (ref "R28")
      (value "33k")
      (footprint "eagle-import:R0402")
      (libsource (lib "eagle-import") (part "R-US_R0402"))
    )
    (comp (ref "R46")
      (value "1.0k")
      (footprint "eagle-import:R0603")
      (libsource (lib "eagle-import") (part "R-US_R0603"))
    )
    (comp (ref "R47")
      (value "1.0k")
      (footprint "eagle-import:R0603")
      (libsource (lib "eagle-import") (part "R-US_R0603"))
    )
    (comp (ref "C1")
      (value "22u")
      (footprint "eagle-import:C1206")
      (libsource (lib "eagle-import") (part "C-USC1206"))
    )
    (comp (ref "C2")
      (value "22u")
      (footprint "eagle-import:C1206")
      (libsource (lib "eagle-import") (part "C-USC1206"))
    )
    (comp (ref "C3")
      (value "10u")
      (footprint "eagle-import:PANASONIC_A")
      (libsource (lib "eagle-import") (part "CPOL-USA"))
    )
    (comp (ref "C4")
      (value "22u")
      (footprint "eagle-import:PANASONIC_B")
      (libsource (lib "eagle-import") (part "CPOL-USB"))
    )
    (comp (ref "C5")
      (value "22u")
      (footprint "eagle-import:PANASONIC_B")
      (libsource (lib "eagle-import") (part "CPOL-USB"))
    )
    (comp (ref "C6")
      (value "100n")
      (footprint "eagle-import:C0402")
      (libsource (lib "eagle-import") (part "C-USC0402"))
    )
    (comp (ref "C13")
      (value "22u")
      (footprint "eagle-import:C1206")
      (libsource (lib "eagle-import") (part "C-USC1206"))
    )
    (comp (ref "C22")
      (value "10u")
      (footprint "eagle-import:PANASONIC_A")
      (libsource (lib "eagle-import") (part "CPOL-USA"))
    )
    (comp (ref "C50")
      (value "1u")
      (footprint "eagle-import:C0402")
      (libsource (lib "eagle-import") (part "C-USC0402"))
    )
    (comp (ref "D1")
      (value "1N5819HW")
      (footprint "eagle-import:SOD123")
      (libsource (lib "eagle-import") (part "DIODE-SOD123"))
    )
    (comp (ref "D2")
      (value "1N5819HW")
      (footprint "eagle-import:SOD123")
      (libsource (lib "eagle-import") (part "DIODE-SOD123"))
    )
    (comp (ref "H2")
      (value "MOUNT-HOLE")
      (footprint "eagle-import:3,0TINY")
      (libsource (lib "eagle-import") (part "MOUNT-HOLE3.0TINY"))
    )
    (comp (ref "H3")
      (value "MOUNT-HOLE")
      (footprint "eagle-import:3,0TINY")
      (libsource (lib "eagle-import") (part "MOUNT-HOLE3.0TINY"))
    )
    (comp (ref "IC1")
      (value "R-78E3.3-0.5")
      (footprint "eagle-import:WE78")
      (libsource (lib "eagle-import") (part "WE173950378"))
    )
    (comp (ref "IC3")
      (value "LD2981ABU33")
      (footprint "eagle-import:SOT89")
      (libsource (lib "eagle-import") (part "LD2981ABU"))
    )
    (comp (ref "IC9")
      (value "LM4040B10")
      (footprint "eagle-import:DBZ_R-PDSO-G3")
      (libsource (lib "eagle-import") (part "LM4041DBZB12"))
    )
    (comp (ref "JP8")
      (value "M05X2SHD")
      (footprint "eagle-import:2X5-SHROUDED")
      (libsource (lib "eagle-import") (part "M05X2SHD"))
    )
    (comp (ref "L1")
      (value "33u")
      (footprint "eagle-import:L2012C")
      (libsource (lib "eagle-import") (part "L-USL2012C"))
    )
    (comp (ref "L2")
      (value "WE-CBF_0603")
      (footprint "eagle-import:0603")
      (libsource (lib "eagle-import") (part "WE-CBF_0603"))
    )
    (comp (ref "L3")
      (value "WE-CBF_0603")
      (footprint "eagle-import:0603")
      (libsource (lib "eagle-import") (part "WE-CBF_0603"))
    )
    (comp (ref "L5")
      (value "WE-CBF_0603")
      (footprint "eagle-import:0603")
      (libsource (lib "eagle-import") (part "WE-CBF_0603"))
    )
    (comp (ref "R37")
      (value "2.2k")
      (footprint "eagle-import:R0402")
      (libsource (lib "eagle-import") (part "R-US_R0402"))
    )
    (comp (ref "C9")
      (value "1u")
      (footprint "eagle-import:C0402")
      (libsource (lib "eagle-import") (part "C-USC0402"))
    )
    (comp (ref "C10")
      (value "100n")
      (footprint "eagle-import:C0402")
      (libsource (lib "eagle-import") (part "C-USC0402"))
    )
    (comp (ref "C14")
      (value "20p")
      (footprint "eagle-import:C0402")
      (libsource (lib "eagle-import") (part "C-USC0402"))
    )
    (comp (ref "C15")
      (value "100n")
      (footprint "eagle-import:C0402")
      (libsource (lib "eagle-import") (part "C-USC0402"))
    )
    (comp (ref "C19")
      (value "1u")
      (footprint "eagle-import:C0402")
      (libsource (lib "eagle-import") (part "C-USC0402"))
    )
    (comp (ref "C20")
      (value "100n")
      (footprint "eagle-import:C0402")
      (libsource (lib "eagle-import") (part "C-USC0402"))
    )
    (comp (ref "C21")
      (value "20p")
      (footprint "eagle-import:C0402")
      (libsource (lib "eagle-import") (part "C-USC0402"))
    )
    (comp (ref "C23")
      (value "100n")
      (footprint "eagle-import:C0402")
      (libsource (lib "eagle-import") (part "C-USC0402"))
    )
    (comp (ref "C24")
      (value "1u")
      (footprint "eagle-import:C0402")
      (libsource (lib "eagle-import") (part "C-USC0402"))
    )
    (comp (ref "C25")
      (value "1u")
      (footprint "eagle-import:C0402")
      (libsource (lib "eagle-import") (part "C-USC0402"))
    )
    (comp (ref "C26")
      (value "100n")
      (footprint "eagle-import:C0402")
      (libsource (lib "eagle-import") (part "C-USC0402"))
    )
    (comp (ref "IC4")
      (value "STM32F373CCT6")
      (footprint "eagle-import:LQFP48")
      (libsource (lib "eagle-import") (part "STM32F373C"))
    )
    (comp (ref "JP5")
      (value "M02PTH")
      (footprint "eagle-import:1X02")
      (libsource (lib "eagle-import") (part "M02PTH"))
    )
    (comp (ref "JP6")
      (value "M04PTH")
      (footprint "eagle-import:1X04")
      (libsource (lib "eagle-import") (part "M04PTH"))
    )
    (comp (ref "Q1")
      (value "8MHz")
      (footprint "eagle-import:CTS406")
      (libsource (lib "eagle-import") (part "CRYSTAL"))
    )
    (comp (ref "R4")
      (value "10k")
      (footprint "eagle-import:R0402")
      (libsource (lib "eagle-import") (part "R-US_R0402"))
    )
    (comp (ref "R5")
      (value "100")
      (footprint "eagle-import:R0402")
      (libsource (lib "eagle-import") (part "R-US_R0402"))
    )
    (comp (ref "R6")
      (value "100")
      (footprint "eagle-import:R0402")
      (libsource (lib "eagle-import") (part "R-US_R0402"))
    )
    (comp (ref "R9")
      (value "100")
      (footprint "eagle-import:R0402")
      (libsource (lib "eagle-import") (part "R-US_R0402"))
    )
    (comp (ref "R10")
      (value "100")
      (footprint "eagle-import:R0402")
      (libsource (lib "eagle-import") (part "R-US_R0402"))
    )
  )
  (nets
    (net (code "1") (name "+3V3") (class "Default")
      (node (ref "C10") (pin "1") (pinfunction "1_1") (pintype "passive"))
      (node (ref "C16") (pin "+") (pinfunction "+_+") (pintype "passive"))
      (node (ref "C17") (pin "1") (pinfunction "1_1") (pintype "passive"))
      (node (ref "C25") (pin "1") (pinfunction "1_1") (pintype "passive"))
      (node (ref "C26") (pin "1") (pinfunction "1_1") (pintype "passive"))
      (node (ref "C3") (pin "+") (pinfunction "+_+") (pintype "passive"))
      (node (ref "C6") (pin "1") (pinfunction "1_1") (pintype "passive"))
      (node (ref "C9") (pin "1") (pinfunction "1_1") (pintype "passive"))
      (node (ref "D3") (pin "2") (pinfunction "C_2") (pintype "passive"))
      (node (ref "IC1") (pin "3") (pinfunction "VO_3") (pintype "passive"))
      (node (ref "IC4") (pin "1") (pinfunction "VBAT_1") (pintype "power_in"))
      (node (ref "IC4") (pin "17") (pinfunction "VDD_2_17") (pintype "power_in"))
      (node (ref "IC4") (pin "48") (pinfunction "VDD_1_48") (pintype "power_in"))
      (node (ref "IC5") (pin "11") (pinfunction "FLT_11") (pintype "input"))
      (node (ref "IC5") (pin "17") (pinfunction "XSMT_17") (pintype "input"))
      (node (ref "IC5") (pin "20") (pinfunction "DVDD_20") (pintype "power_in"))
      (node (ref "L4") (pin "2") (pinfunction "2_2") (pintype "passive"))
      (node (ref "LED1") (pin "A") (pinfunction "A_A") (pintype "bidirectional"))
      (node (ref "LED2") (pin "A") (pinfunction "A_A") (pintype "bidirectional"))
      (node (ref "LED3") (pin "A") (pinfunction "A_A") (pintype "bidirectional"))
      (node (ref "LED4") (pin "A") (pinfunction "A_A") (pintype "bidirectional"))
      (node (ref "LED5") (pin "A") (pinfunction "A_A") (pintype "bidirectional"))
      (node (ref "LED6") (pin "A") (pinfunction "A_A") (pintype "bidirectional"))
      (node (ref "LED7") (pin "A") (pinfunction "A_A") (pintype "bidirectional"))
      (node (ref "LED8") (pin "A") (pinfunction "A_A") (pintype "bidirectional"))
      (node (ref "R4") (pin "1") (pinfunction "1_1") (pintype "passive"))
    )
    (net (code "2") (name "+3V3_A") (class "Default")
      (node (ref "C19") (pin "1") (pinfunction "1_1") (pintype "passive"))
      (node (ref "C20") (pin "1") (pinfunction "1_1") (pintype "passive"))
      (node (ref "C22") (pin "+") (pinfunction "+_+") (pintype "passive"))
      (node (ref "C23") (pin "1") (pinfunction "1_1") (pintype "passive"))
      (node (ref "C24") (pin "1") (pinfunction "1_1") (pintype "passive"))
      (node (ref "C27") (pin "1") (pinfunction "1_1") (pintype "passive"))
      (node (ref "C28") (pin "1") (pinfunction "1_1") (pintype "passive"))
      (node (ref "C30") (pin "+") (pinfunction "+_+") (pintype "passive"))
      (node (ref "C36") (pin "1") (pinfunction "1_1") (pintype "passive"))
      (node (ref "C44") (pin "1") (pinfunction "1_1") (pintype "passive"))
      (node (ref "IC3") (pin "1") (pinfunction "VO_1") (pintype "passive"))
      (node (ref "IC4") (pin "24") (pinfunction "VDDSD_24") (pintype "power_in"))
      (node (ref "IC4") (pin "25") (pinfunction "VREFSD+_25") (pintype "power_in"))
      (node (ref "IC4") (pin "9") (pinfunction "VDDA_9") (pintype "power_in"))
      (node (ref "IC5") (pin "1") (pinfunction "CPVDD_1") (pintype "bidirectional"))
      (node (ref "IC5") (pin "8") (pinfunction "AVDD_8") (pintype "power_in"))
      (node (ref "IC6") (pin "4") (pinfunction "V+_4") (pintype "power_in"))
      (node (ref "IC7") (pin "4") (pinfunction "V+_4") (pintype "power_in"))
      (node (ref "R1") (pin "P$1") (pinfunction "E_P$1") (pintype "passive"))
      (node (ref "R2") (pin "P$1") (pinfunction "E_P$1") (pintype "passive"))
      (node (ref "R42") (pin "P$1") (pinfunction "E_P$1") (pintype "passive"))
      (node (ref "R43") (pin "P$1") (pinfunction "E_P$1") (pintype "passive"))
      (node (ref "R44") (pin "P$1") (pinfunction "E_P$1") (pintype "passive"))
      (node (ref "R7") (pin "P$1") (pinfunction "E_P$1") (pintype "passive"))
      (node (ref "R8") (pin "P$1") (pinfunction "E_P$1") (pintype "passive"))
    )
    (net (code "3") (name "ADC_FM") (class "Default")
      (node (ref "C40") (pin "2") (pinfunction "2_2") (pintype "passive"))
      (node (ref "IC4") (pin "22") (pinfunction "PE9/SDADC1_AIN7P/SDADC1_AIN8M/SDADC2_AIN7P/SDADC2_AIN8M_22") (pintype "bidirectional"))
      (node (ref "IC7") (pin "1") (pinfunction "OUT_1") (pintype "output"))
      (node (ref "R19") (pin "1") (pinfunction "1_1") (pintype "passive"))
    )
    (net (code "4") (name "ADC_GATE") (class "Default")
      (node (ref "C39") (pin "2") (pinfunction "2_2") (pintype "passive"))
      (node (ref "IC4") (pin "21") (pinfunction "PE8/SDADC1_AIN8P/SDADC2_AIN8P_21") (pintype "bidirectional"))
      (node (ref "IC6") (pin "14") (pinfunction "OUT_14") (pintype "output"))
      (node (ref "R18") (pin "1") (pinfunction "1_1") (pintype "passive"))
    )
    (net (code "5") (name "ADC_HARMONICS") (class "Default")
      (node (ref "C41") (pin "2") (pinfunction "2_2") (pintype "passive"))
      (node (ref "IC4") (pin "28") (pinfunction "PD8/SPI2_SCK/I2S2_CK/USART3_TX/SDADC3_AIN6P_28") (pintype "bidirectional"))
      (node (ref "IC7") (pin "14") (pinfunction "OUT_14") (pintype "output"))
      (node (ref "R20") (pin "1") (pinfunction "1_1") (pintype "passive"))
    )
    (net (code "6") (name "ADC_MODEL") (class "Default")
      (node (ref "C46") (pin "2") (pinfunction "2_2") (pintype "passive"))
      (node (ref "IC4") (pin "19") (pinfunction "PB1/TIM3_CH4/ADC_IN9/SDADC1_AIN5P/SDADC1_AIN6M_19") (pintype "bidirectional"))
      (node (ref "IC6") (pin "7") (pinfunction "OUT_7") (pintype "output"))
      (node (ref "R31") (pin "1") (pinfunction "1_1") (pintype "passive"))
    )
    (net (code "7") (name "ADC_MORPH") (class "Default")
      (node (ref "C49") (pin "2") (pinfunction "2_2") (pintype "passive"))
      (node (ref "IC4") (pin "27") (pinfunction "PB15/SPI2_MOSI/I2S2_SD/SDADC3_AIN7P/SDADC3_AIN8M_27") (pintype "bidirectional"))
      (node (ref "IC7") (pin "8") (pinfunction "OUT_8") (pintype "output"))
      (node (ref "R35") (pin "1") (pinfunction "1_1") (pintype "passive"))
    )
    (net (code "8") (name "ADC_TIMBRE") (class "Default")
      (node (ref "C47") (pin "2") (pinfunction "2_2") (pintype "passive"))
      (node (ref "IC4") (pin "20") (pinfunction "PB2/SDADC1_AIN4P/SDADC2_AIN6P_20") (pintype "bidirectional"))
      (node (ref "IC6") (pin "8") (pinfunction "OUT_8") (pintype "output"))
      (node (ref "R32") (pin "1") (pinfunction "1_1") (pintype "passive"))
    )
    (net (code "9") (name "ADC_TRIG") (class "Default")
      (node (ref "C38") (pin "2") (pinfunction "2_2") (pintype "passive"))
      (node (ref "IC4") (pin "18") (pinfunction "PB0/SPI1_MOSI/I2S1_SD/TIM3_CH3/ADC_IN8/SDADC1_AIN6P_18") (pintype "bidirectional"))
      (node (ref "IC6") (pin "1") (pinfunction "OUT_1") (pintype "output"))
      (node (ref "R17") (pin "1") (pinfunction "1_1") (pintype "passive"))
    )
    (net (code "10") (name "ADC_V_OCT") (class "Default")
      (node (ref "C48") (pin "2") (pinfunction "2_2") (pintype "passive"))
      (node (ref "IC4") (pin "26") (pinfunction "PB14/SPI2_MISO/I2S2_MCK/USART3_RTS/SDADC3_AIN8P_26") (pintype "bidirectional"))
      (node (ref "IC7") (pin "7") (pinfunction "OUT_7") (pintype "output"))
      (node (ref "R34") (pin "1") (pinfunction "1_1") (pintype "passive"))
    )
    (net (code "11") (name "AREF_-10") (class "Default")
      (node (ref "C50") (pin "1") (pinfunction "1_1") (pintype "passive"))
      (node (ref "IC9") (pin "2") (pinfunction "A_2") (pintype "passive"))
      (node (ref "R23") (pin "2") (pinfunction "2_2") (pintype "passive"))
      (node (ref "R25") (pin "2") (pinfunction "2_2") (pintype "passive"))
      (node (ref "R26") (pin "2") (pinfunction "2_2") (pintype "passive"))
      (node (ref "R27") (pin "2") (pinfunction "2_2") (pintype "passive"))
      (node (ref "R29") (pin "2") (pinfunction "2_2") (pintype "passive"))
      (node (ref "R30") (pin "2") (pinfunction "2_2") (pintype "passive"))
      (node (ref "R33") (pin "2") (pinfunction "2_2") (pintype "passive"))
      (node (ref "R36") (pin "2") (pinfunction "2_2") (pintype "passive"))
      (node (ref "R37") (pin "2") (pinfunction "2_2") (pintype "passive"))
    )
    (net (code "12") (name "DAC_BCK") (class "Default")
      (node (ref "IC4") (pin "29") (pinfunction "PA8/SPI2_SCK/I2S2_CK/I2C2_SMBA/USART1_CK/TIM5_CH1_29") (pintype "bidirectional"))
      (node (ref "IC5") (pin "13") (pinfunction "BCK_13") (pintype "input"))
    )
    (net (code "13") (name "DAC_DIN") (class "Default")
      (node (ref "IC4") (pin "31") (pinfunction "PA10/SPI2_MOSI/I2S2_SD/I2C2_SDA/USART1_RX/TIM2_CH4_31") (pintype "bidirectional"))
      (node (ref "IC5") (pin "14") (pinfunction "DIN_14") (pintype "input"))
    )
    (net (code "14") (name "DAC_LRCK") (class "Default")
      (node (ref "IC4") (pin "32") (pinfunction "PA11/SPI2_NSS/I2S2_WS/SPI1_NSS/I2S1_WS/USART1_CTS/CAN_RX/TIM4_CH1/TIM5_CH2_32") (pintype "bidirectional"))
      (node (ref "IC5") (pin "15") (pinfunction "LRCK_15") (pintype "input"))
    )
    (net (code "15") (name "FREQ_ATT") (class "Default")
      (node (ref "C51") (pin "1") (pinfunction "1_1") (pintype "passive"))
      (node (ref "IC4") (pin "15") (pinfunction "PA5/SPI1_SCK/I2S1_CK/TIM2_CH1/ADC_IN5/DAC1_OUT2_15") (pintype "bidirectional"))
      (node (ref "R43") (pin "P$2") (pinfunction "S_P$2") (pintype "passive"))
    )
    (net (code "16") (name "FREQ_POT") (class "Default")
      (node (ref "C11") (pin "1") (pinfunction "1_1") (pintype "passive"))
      (node (ref "IC4") (pin "10") (pinfunction "PA0/USART2_CTS/TIM2_CH1/TIM5_CH1/ADC_IN0_10") (pintype "bidirectional"))
      (node (ref "R1") (pin "P$2") (pinfunction "S_P$2") (pintype "passive"))
    )
    (net (code "17") (name "GND") (class "Default")
      (node (ref "C1") (pin "2") (pinfunction "2_2") (pintype "passive"))
      (node (ref "C10") (pin "2") (pinfunction "2_2") (pintype "passive"))
      (node (ref "C11") (pin "2") (pinfunction "2_2") (pintype "passive"))
      (node (ref "C12") (pin "2") (pinfunction "2_2") (pintype "passive"))
      (node (ref "C13") (pin "2") (pinfunction "2_2") (pintype "passive"))
      (node (ref "C14") (pin "1") (pinfunction "1_1") (pintype "passive"))
      (node (ref "C15") (pin "2") (pinfunction "2_2") (pintype "passive"))
      (node (ref "C16") (pin "-") (pinfunction "-_-") (pintype "passive"))
      (node (ref "C17") (pin "2") (pinfunction "2_2") (pintype "passive"))
      (node (ref "C18") (pin "2") (pinfunction "2_2") (pintype "passive"))
      (node (ref "C19") (pin "2") (pinfunction "2_2") (pintype "passive"))
      (node (ref "C2") (pin "2") (pinfunction "2_2") (pintype "passive"))
      (node (ref "C20") (pin "2") (pinfunction "2_2") (pintype "passive"))
      (node (ref "C21") (pin "1") (pinfunction "1_1") (pintype "passive"))
      (node (ref "C22") (pin "-") (pinfunction "-_-") (pintype "passive"))
      (node (ref "C23") (pin "2") (pinfunction "2_2") (pintype "passive"))
      (node (ref "C24") (pin "2") (pinfunction "2_2") (pintype "passive"))
      (node (ref "C25") (pin "2") (pinfunction "2_2") (pintype "passive"))
      (node (ref "C26") (pin "2") (pinfunction "2_2") (pintype "passive"))
      (node (ref "C27") (pin "2") (pinfunction "2_2") (pintype "passive"))
      (node (ref "C28") (pin "2") (pinfunction "2_2") (pintype "passive"))
      (node (ref "C3") (pin "-") (pinfunction "-_-") (pintype "passive"))
      (node (ref "C30") (pin "-") (pinfunction "-_-") (pintype "passive"))
      (node (ref "C31") (pin "2") (pinfunction "2_2") (pintype "passive"))
      (node (ref "C32") (pin "2") (pinfunction "2_2") (pintype "passive"))
      (node (ref "C33") (pin "2") (pinfunction "2_2") (pintype "passive"))
      (node (ref "C34") (pin "2") (pinfunction "2_2") (pintype "passive"))
      (node (ref "C35") (pin "2") (pinfunction "2_2") (pintype "passive"))
      (node (ref "C36") (pin "2") (pinfunction "2_2") (pintype "passive"))
      (node (ref "C37") (pin "2") (pinfunction "2_2") (pintype "passive"))
      (node (ref "C4") (pin "-") (pinfunction "-_-") (pintype "passive"))
      (node (ref "C44") (pin "2") (pinfunction "2_2") (pintype "passive"))
      (node (ref "C45") (pin "1") (pinfunction "1_1") (pintype "passive"))
      (node (ref "C5") (pin "+") (pinfunction "+_+") (pintype "passive"))
      (node (ref "C50") (pin "2") (pinfunction "2_2") (pintype "passive"))
      (node (ref "C51") (pin "2") (pinfunction "2_2") (pintype "passive"))
      (node (ref "C52") (pin "2") (pinfunction "2_2") (pintype "passive"))
      (node (ref "C53") (pin "2") (pinfunction "2_2") (pintype "passive"))
      (node (ref "C54") (pin "2") (pinfunction "2_2") (pintype "passive"))
      (node (ref "C55") (pin "2") (pinfunction "2_2") (pintype "passive"))
      (node (ref "C56") (pin "2") (pinfunction "2_2") (pintype "passive"))
      (node (ref "C57") (pin "2") (pinfunction "2_2") (pintype "passive"))
      (node (ref "C58") (pin "2") (pinfunction "2_2") (pintype "passive"))
      (node (ref "C59") (pin "2") (pinfunction "2_2") (pintype "passive"))
      (node (ref "C6") (pin "2") (pinfunction "2_2") (pintype "passive"))
      (node (ref "C60") (pin "2") (pinfunction "2_2") (pintype "passive"))
      (node (ref "C61") (pin "2") (pinfunction "2_2") (pintype "passive"))
      (node (ref "C7") (pin "-") (pinfunction "-_-") (pintype "passive"))
      (node (ref "C8") (pin "2") (pinfunction "2_2") (pintype "passive"))
      (node (ref "C9") (pin "2") (pinfunction "2_2") (pintype "passive"))
      (node (ref "D3") (pin "1") (pinfunction "A_1") (pintype "passive"))
      (node (ref "IC1") (pin "2") (pinfunction "GND_2") (pintype "passive"))
      (node (ref "IC2") (pin "1") (pinfunction "GND_1") (pintype "bidirectional"))
      (node (ref "IC2") (pin "21") (pinfunction "BLANK_21") (pintype "bidirectional"))
      (node (ref "IC3") (pin "2") (pinfunction "GND_2") (pintype "passive"))
      (node (ref "IC4") (pin "23") (pinfunction "VSSSD/VREFSD-_23") (pintype "power_in"))
      (node (ref "IC4") (pin "44") (pinfunction "BOOT0_44") (pintype "bidirectional"))
      (node (ref "IC4") (pin "47") (pinfunction "VSS_1_47") (pintype "power_in"))
      (node (ref "IC4") (pin "8") (pinfunction "VSSA_8") (pintype "power_in"))
      (node (ref "IC5") (pin "10") (pinfunction "DEMP_10") (pintype "input"))
      (node (ref "IC5") (pin "12") (pinfunction "SCK_12") (pintype "input"))
      (node (ref "IC5") (pin "16") (pinfunction "FMT_16") (pintype "input"))
      (node (ref "IC5") (pin "19") (pinfunction "DGND_19") (pintype "power_in"))
      (node (ref "IC5") (pin "3") (pinfunction "CPGND_3") (pintype "bidirectional"))
      (node (ref "IC5") (pin "9") (pinfunction "AGND_9") (pintype "power_in"))
      (node (ref "IC6") (pin "10") (pinfunction "+IN_10") (pintype "input"))
      (node (ref "IC6") (pin "11") (pinfunction "V-_11") (pintype "power_in"))
      (node (ref "IC6") (pin "12") (pinfunction "+IN_12") (pintype "input"))
      (node (ref "IC6") (pin "3") (pinfunction "+IN_3") (pintype "input"))
      (node (ref "IC6") (pin "5") (pinfunction "+IN_5") (pintype "input"))
      (node (ref "IC7") (pin "10") (pinfunction "+IN_10") (pintype "input"))
      (node (ref "IC7") (pin "11") (pinfunction "V-_11") (pintype "power_in"))
      (node (ref "IC7") (pin "12") (pinfunction "+IN_12") (pintype "input"))
      (node (ref "IC7") (pin "3") (pinfunction "+IN_3") (pintype "input"))
      (node (ref "IC7") (pin "5") (pinfunction "+IN_5") (pintype "input"))
      (node (ref "IC8") (pin "3") (pinfunction "+IN_3") (pintype "input"))
      (node (ref "IC8") (pin "5") (pinfunction "+IN_5") (pintype "input"))
      (node (ref "IC9") (pin "1") (pinfunction "C_1") (pintype "passive"))
      (node (ref "J1") (pin "P1") (pinfunction "1_P1") (pintype "passive"))
      (node (ref "J1") (pin "P2") (pinfunction "2_P2") (pintype "passive"))
      (node (ref "J10") (pin "P1") (pinfunction "1_P1") (pintype "passive"))
      (node (ref "J2") (pin "P1") (pinfunction "1_P1") (pintype "passive"))
      (node (ref "J3") (pin "P1") (pinfunction "1_P1") (pintype "passive"))
      (node (ref "J4") (pin "P1") (pinfunction "1_P1") (pintype "passive"))
      (node (ref "J5") (pin "P1") (pinfunction "1_P1") (pintype "passive"))
      (node (ref "J5") (pin "P2") (pinfunction "2_P2") (pintype "passive"))
      (node (ref "J6") (pin "P1") (pinfunction "1_P1") (pintype "passive"))
      (node (ref "J7") (pin "P1") (pinfunction "1_P1") (pintype "passive"))
      (node (ref "J8") (pin "P1") (pinfunction "1_P1") (pintype "passive"))
      (node (ref "J8") (pin "P2") (pinfunction "2_P2") (pintype "passive"))
      (node (ref "J9") (pin "P1") (pinfunction "1_P1") (pintype "passive"))
      (node (ref "JP6") (pin "1") (pinfunction "1_1") (pintype "passive"))
      (node (ref "JP8") (pin "3") (pinfunction "3_3") (pintype "passive"))
      (node (ref "JP8") (pin "4") (pinfunction "4_4") (pintype "passive"))
      (node (ref "JP8") (pin "5") (pinfunction "5_5") (pintype "passive"))
      (node (ref "JP8") (pin "6") (pinfunction "6_6") (pintype "passive"))
      (node (ref "JP8") (pin "7") (pinfunction "7_7") (pintype "passive"))
      (node (ref "JP8") (pin "8") (pinfunction "8_8") (pintype "passive"))
      (node (ref "Q1") (pin "2") (pinfunction "LID1_2") (pintype "power_in"))
      (node (ref "Q1") (pin "4") (pinfunction "LID2_4") (pintype "power_in"))
      (node (ref "R1") (pin "P$3") (pinfunction "A_P$3") (pintype "passive"))
      (node (ref "R2") (pin "P$3") (pinfunction "A_P$3") (pintype "passive"))
      (node (ref "R3") (pin "2") (pinfunction "2_2") (pintype "passive"))
      (node (ref "R42") (pin "P$3") (pinfunction "A_P$3") (pintype "passive"))
      (node (ref "R43") (pin "P$3") (pinfunction "A_P$3") (pintype "passive"))
      (node (ref "R44") (pin "P$3") (pinfunction "A_P$3") (pintype "passive"))
      (node (ref "R7") (pin "P$3") (pinfunction "A_P$3") (pintype "passive"))
      (node (ref "R8") (pin "P$3") (pinfunction "A_P$3") (pintype "passive"))
      (node (ref "SW1") (pin "1") (pinfunction "1_1") (pintype "passive"))
      (node (ref "SW1") (pin "2") (pinfunction "2_2") (pintype "passive"))
      (node (ref "SW2") (pin "1") (pinfunction "1_1") (pintype "passive"))
      (node (ref "SW2") (pin "2") (pinfunction "2_2") (pintype "passive"))
    )
    (net (code "18") (name "HARMONICS_POT") (class "Default")
      (node (ref "C12") (pin "1") (pinfunction "1_1") (pintype "passive"))
      (node (ref "IC4") (pin "12") (pinfunction "PA2/SPI3_MISO/I2S3_MCK/USART2_TX/TIM2_CH3/TIM5_CH3/ADC_IN2_12") (pintype "bidirectional"))
      (node (ref "R2") (pin "P$2") (pinfunction "S_P$2") (pintype "passive"))
    )
    (net (code "19") (name "LEDS_SCK") (class "Default")
      (node (ref "IC2") (pin "3") (pinfunction "SCLK_3") (pintype "bidirectional"))
      (node (ref "IC4") (pin "33") (pinfunction "PA12/SPI1_SCK/I2S1_CK/USART1_RTS/CAN_TX/TIM4_CH2/TIM5_CH3_33") (pintype "bidirectional"))
    )
    (net (code "20") (name "LEDS_SIN") (class "Default")
      (node (ref "IC2") (pin "2") (pinfunction "SIN_2") (pintype "bidirectional"))
      (node (ref "IC4") (pin "35") (pinfunction "PF6/SPI1_MOSI/I2S1_SD/USART3_RTS/TIM4_CH4/I2C2_SCL_35") (pintype "bidirectional"))
    )
    (net (code "21") (name "LEDS_SS") (class "Default")
      (node (ref "IC2") (pin "4") (pinfunction "LAT_4") (pintype "bidirectional"))
      (node (ref "IC4") (pin "36") (pinfunction "PF7/I2C2_SDA/USART2_CK_36") (pintype "bidirectional"))
    )
    (net (code "22") (name "MORPH_ATT") (class "Default")
      (node (ref "C52") (pin "1") (pinfunction "1_1") (pintype "passive"))
      (node (ref "IC4") (pin "14") (pinfunction "PA4/SPI1_NSS/I2S1_WS/SPI3_NSS/I2S3_WS/USART2_CK/TIM3_CH2/ADC_IN4/DAC1_OUT1_14") (pintype "bidirectional"))
      (node (ref "R44") (pin "P$2") (pinfunction "S_P$2") (pintype "passive"))
    )
    (net (code "23") (name "MORPH_POT") (class "Default")
      (node (ref "C34") (pin "1") (pinfunction "1_1") (pintype "passive"))
      (node (ref "IC4") (pin "11") (pinfunction "PA1/SPI3_SCK/I2S3_CK/USART2_RTS/TIM2_CH2/TIM5_CH2/ADC_IN1_11") (pintype "bidirectional"))
      (node (ref "R8") (pin "P$2") (pinfunction "S_P$2") (pintype "passive"))
    )
    (net (code "24") (name "NORMALIZATION_PROBE") (class "Default")
      (node (ref "D3") (pin "3") (pinfunction "AC_3") (pintype "passive"))
      (node (ref "IC4") (pin "30") (pinfunction "PA9/SPI_MISO/I2S2_MCK/I2C2_SCL/USART1_TX/TIM2_CH3_30") (pintype "bidirectional"))
      (node (ref "R45") (pin "2") (pinfunction "2_2") (pintype "passive"))
      (node (ref "R48") (pin "2") (pinfunction "2_2") (pintype "passive"))
      (node (ref "R49") (pin "2") (pinfunction "2_2") (pintype "passive"))
      (node (ref "R50") (pin "1") (pinfunction "1_1") (pintype "passive"))
      (node (ref "R51") (pin "2") (pinfunction "2_2") (pintype "passive"))
    )
    (net (code "25") (name "Net-(C2-Pad1)") (class "Default")
      (node (ref "C2") (pin "1") (pinfunction "1_1") (pintype "passive"))
      (node (ref "D1") (pin "C") (pinfunction "C_C") (pintype "passive"))
      (node (ref "L1") (pin "1") (pinfunction "1_1") (pintype "passive"))
      (node (ref "L2") (pin "2") (pinfunction "2_2") (pintype "passive"))
      (node (ref "L5") (pin "2") (pinfunction "2_2") (pintype "passive"))
    )
    (net (code "26") (name "Net-(C21-Pad2)") (class "Default")
      (node (ref "C21") (pin "2") (pinfunction "2_2") (pintype "passive"))
      (node (ref "Q1") (pin "1") (pinfunction "1_1") (pintype "passive"))
      (node (ref "R6") (pin "2") (pinfunction "2_2") (pintype "passive"))
    )
    (net (code "27") (name "Net-(C33-Pad1)") (class "Default")
      (node (ref "C33") (pin "1") (pinfunction "1_1") (pintype "passive"))
      (node (ref "R11") (pin "1") (pinfunction "1_1") (pintype "passive"))
      (node (ref "R21") (pin "2") (pinfunction "2_2") (pintype "passive"))
    )
    (net (code "28") (name "Net-(C35-Pad1)") (class "Default")
      (node (ref "C35") (pin "1") (pinfunction "1_1") (pintype "passive"))
      (node (ref "R12") (pin "1") (pinfunction "1_1") (pintype "passive"))
      (node (ref "R16") (pin "2") (pinfunction "2_2") (pintype "passive"))
    )
    (net (code "29") (name "Net-(D1-PadA)") (class "Default")
      (node (ref "D1") (pin "A") (pinfunction "A_A") (pintype "passive"))
      (node (ref "JP8") (pin "10") (pinfunction "10_10") (pintype "passive"))
      (node (ref "JP8") (pin "9") (pinfunction "9_9") (pintype "passive"))
    )
    (net (code "30") (name "Net-(D2-PadA)") (class "Default")
      (node (ref "D2") (pin "A") (pinfunction "A_A") (pintype "passive"))
      (node (ref "L3") (pin "2") (pinfunction "2_2") (pintype "passive"))
    )
    (net (code "31") (name "Net-(D2-PadC)") (class "Default")
      (node (ref "D2") (pin "C") (pinfunction "C_C") (pintype "passive"))
      (node (ref "JP8") (pin "1") (pinfunction "1_1") (pintype "passive"))
      (node (ref "JP8") (pin "2") (pinfunction "2_2") (pintype "passive"))
    )
    (net (code "32") (name "Net-(IC1-VI)") (class "Default")
      (node (ref "C1") (pin "1") (pinfunction "1_1") (pintype "passive"))
      (node (ref "IC1") (pin "1") (pinfunction "VI_1") (pintype "input"))
      (node (ref "L1") (pin "2") (pinfunction "2_2") (pintype "passive"))
    )
    (net (code "33") (name "Net-(IC2-IREF)") (class "Default")
      (node (ref "IC2") (pin "23") (pinfunction "IREF_23") (pintype "bidirectional"))
      (node (ref "R3") (pin "1") (pinfunction "1_1") (pintype "passive"))
    )
    (net (code "34") (name "Net-(IC2-OUT0)") (class "Default")
      (node (ref "IC2") (pin "5") (pinfunction "OUT0_5") (pintype "bidirectional"))
      (node (ref "LED5") (pin "RED_C") (pinfunction "RED_RED_C") (pintype "bidirectional"))
    )
    (net (code "35") (name "Net-(IC2-OUT1)") (class "Default")
      (node (ref "IC2") (pin "6") (pinfunction "OUT1_6") (pintype "bidirectional"))
      (node (ref "LED5") (pin "GREEN_C") (pinfunction "GRN_GREEN_C") (pintype "bidirectional"))
    )
    (net (code "36") (name "Net-(IC2-OUT2)") (class "Default")
      (node (ref "IC2") (pin "7") (pinfunction "OUT2_7") (pintype "bidirectional"))
      (node (ref "LED6") (pin "RED_C") (pinfunction "RED_RED_C") (pintype "bidirectional"))
    )
    (net (code "37") (name "Net-(IC2-OUT3)") (class "Default")
      (node (ref "IC2") (pin "8") (pinfunction "OUT3_8") (pintype "bidirectional"))
      (node (ref "LED6") (pin "GREEN_C") (pinfunction "GRN_GREEN_C") (pintype "bidirectional"))
    )
    (net (code "38") (name "Net-(IC2-OUT4)") (class "Default")
      (node (ref "IC2") (pin "9") (pinfunction "OUT4_9") (pintype "bidirectional"))
      (node (ref "LED7") (pin "RED_C") (pinfunction "RED_RED_C") (pintype "bidirectional"))
    )
    (net (code "39") (name "Net-(IC2-OUT5)") (class "Default")
      (node (ref "IC2") (pin "10") (pinfunction "OUT5_10") (pintype "bidirectional"))
      (node (ref "LED7") (pin "GREEN_C") (pinfunction "GRN_GREEN_C") (pintype "bidirectional"))
    )
    (net (code "40") (name "Net-(IC2-OUT6)") (class "Default")
      (node (ref "IC2") (pin "11") (pinfunction "OUT6_11") (pintype "bidirectional"))
      (node (ref "LED8") (pin "RED_C") (pinfunction "RED_RED_C") (pintype "bidirectional"))
    )
    (net (code "41") (name "Net-(IC2-OUT7)") (class "Default")
      (node (ref "IC2") (pin "12") (pinfunction "OUT7_12") (pintype "bidirectional"))
      (node (ref "LED8") (pin "GREEN_C") (pinfunction "GRN_GREEN_C") (pintype "bidirectional"))
    )
    (net (code "42") (name "Net-(IC2-OUT8)") (class "Default")
      (node (ref "IC2") (pin "13") (pinfunction "OUT8_13") (pintype "bidirectional"))
      (node (ref "LED4") (pin "RED_C") (pinfunction "RED_RED_C") (pintype "bidirectional"))
    )
    (net (code "43") (name "Net-(IC2-OUT9)") (class "Default")
      (node (ref "IC2") (pin "14") (pinfunction "OUT9_14") (pintype "bidirectional"))
      (node (ref "LED4") (pin "GREEN_C") (pinfunction "GRN_GREEN_C") (pintype "bidirectional"))
    )
    (net (code "44") (name "Net-(IC2-OUT10)") (class "Default")
      (node (ref "IC2") (pin "15") (pinfunction "OUT10_15") (pintype "bidirectional"))
      (node (ref "LED3") (pin "RED_C") (pinfunction "RED_RED_C") (pintype "bidirectional"))
    )
    (net (code "45") (name "Net-(IC2-OUT11)") (class "Default")
      (node (ref "IC2") (pin "16") (pinfunction "OUT11_16") (pintype "bidirectional"))
      (node (ref "LED3") (pin "GREEN_C") (pinfunction "GRN_GREEN_C") (pintype "bidirectional"))
    )
    (net (code "46") (name "Net-(IC2-OUT12)") (class "Default")
      (node (ref "IC2") (pin "17") (pinfunction "OUT12_17") (pintype "bidirectional"))
      (node (ref "LED2") (pin "RED_C") (pinfunction "RED_RED_C") (pintype "bidirectional"))
    )
    (net (code "47") (name "Net-(IC2-OUT13)") (class "Default")
      (node (ref "IC2") (pin "18") (pinfunction "OUT13_18") (pintype "bidirectional"))
      (node (ref "LED2") (pin "GREEN_C") (pinfunction "GRN_GREEN_C") (pintype "bidirectional"))
    )
    (net (code "48") (name "Net-(IC2-OUT14)") (class "Default")
      (node (ref "IC2") (pin "19") (pinfunction "OUT14_19") (pintype "bidirectional"))
      (node (ref "LED1") (pin "RED_C") (pinfunction "RED_RED_C") (pintype "bidirectional"))
    )
    (net (code "49") (name "Net-(IC2-OUT15)") (class "Default")
      (node (ref "IC2") (pin "20") (pinfunction "OUT15_20") (pintype "bidirectional"))
      (node (ref "LED1") (pin "GREEN_C") (pinfunction "GRN_GREEN_C") (pintype "bidirectional"))
    )
    (net (code "50") (name "Net-(IC2-VCC)") (class "Default")
      (node (ref "C7") (pin "+") (pinfunction "+_+") (pintype "passive"))
      (node (ref "C8") (pin "1") (pinfunction "1_1") (pintype "passive"))
      (node (ref "IC2") (pin "24") (pinfunction "VCC_24") (pintype "bidirectional"))
      (node (ref "L4") (pin "1") (pinfunction "1_1") (pintype "passive"))
    )
    (net (code "51") (name "Net-(IC3-VI)") (class "Default")
      (node (ref "C13") (pin "1") (pinfunction "1_1") (pintype "passive"))
      (node (ref "IC3") (pin "3") (pinfunction "VI_3") (pintype "input"))
      (node (ref "L5") (pin "1") (pinfunction "1_1") (pintype "passive"))
    )
    (net (code "52") (name "Net-(IC4-PF0{slash}OSC_IN{slash}I2C2_SDA)") (class "Default")
      (node (ref "IC4") (pin "5") (pinfunction "PF0/OSC_IN/I2C2_SDA_5") (pintype "bidirectional"))
      (node (ref "R5") (pin "1") (pinfunction "1_1") (pintype "passive"))
    )
    (net (code "53") (name "Net-(IC4-PF1{slash}OSC_OUT{slash}I2C2_SCL)") (class "Default")
      (node (ref "IC4") (pin "6") (pinfunction "PF1/OSC_OUT/I2C2_SCL_6") (pintype "bidirectional"))
      (node (ref "R6") (pin "1") (pinfunction "1_1") (pintype "passive"))
    )
    (net (code "54") (name "Net-(IC5-CAPM)") (class "Default")
      (node (ref "C29") (pin "2") (pinfunction "2_2") (pintype "passive"))
      (node (ref "IC5") (pin "4") (pinfunction "CAPM_4") (pintype "bidirectional"))
    )
    (net (code "55") (name "Net-(IC5-CAPP)") (class "Default")
      (node (ref "C29") (pin "1") (pinfunction "1_1") (pintype "passive"))
      (node (ref "IC5") (pin "2") (pinfunction "CAPP_2") (pintype "bidirectional"))
    )
    (net (code "56") (name "Net-(IC5-LDOO)") (class "Default")
      (node (ref "C18") (pin "1") (pinfunction "1_1") (pintype "passive"))
      (node (ref "IC5") (pin "18") (pinfunction "LDOO_18") (pintype "bidirectional"))
    )
    (net (code "57") (name "Net-(IC5-OUTL)") (class "Default")
      (node (ref "IC5") (pin "6") (pinfunction "OUTL_6") (pintype "output"))
      (node (ref "R11") (pin "2") (pinfunction "2_2") (pintype "passive"))
    )
    (net (code "58") (name "Net-(IC5-OUTR)") (class "Default")
      (node (ref "IC5") (pin "7") (pinfunction "OUTR_7") (pintype "output"))
      (node (ref "R12") (pin "2") (pinfunction "2_2") (pintype "passive"))
    )
    (net (code "59") (name "Net-(IC5-VNEG)") (class "Default")
      (node (ref "C31") (pin "1") (pinfunction "1_1") (pintype "passive"))
      (node (ref "IC5") (pin "5") (pinfunction "VNEG_5") (pintype "input"))
    )
    (net (code "60") (name "Net-(IC6A--IN)") (class "Default")
      (node (ref "C38") (pin "1") (pinfunction "1_1") (pintype "passive"))
      (node (ref "IC6") (pin "2") (pinfunction "-IN_2") (pintype "input"))
      (node (ref "R17") (pin "2") (pinfunction "2_2") (pintype "passive"))
      (node (ref "R24") (pin "1") (pinfunction "1_1") (pintype "passive"))
      (node (ref "R25") (pin "1") (pinfunction "1_1") (pintype "passive"))
    )
    (net (code "61") (name "Net-(IC6B--IN)") (class "Default")
      (node (ref "C46") (pin "1") (pinfunction "1_1") (pintype "passive"))
      (node (ref "IC6") (pin "6") (pinfunction "-IN_6") (pintype "input"))
      (node (ref "R30") (pin "1") (pinfunction "1_1") (pintype "passive"))
      (node (ref "R31") (pin "2") (pinfunction "2_2") (pintype "passive"))
      (node (ref "R40") (pin "1") (pinfunction "1_1") (pintype "passive"))
    )
    (net (code "62") (name "Net-(IC6C--IN)") (class "Default")
      (node (ref "C47") (pin "1") (pinfunction "1_1") (pintype "passive"))
      (node (ref "IC6") (pin "9") (pinfunction "-IN_9") (pintype "input"))
      (node (ref "R32") (pin "2") (pinfunction "2_2") (pintype "passive"))
      (node (ref "R33") (pin "1") (pinfunction "1_1") (pintype "passive"))
      (node (ref "R41") (pin "1") (pinfunction "1_1") (pintype "passive"))
    )
    (net (code "63") (name "Net-(IC6D--IN)") (class "Default")
      (node (ref "C39") (pin "1") (pinfunction "1_1") (pintype "passive"))
      (node (ref "IC6") (pin "13") (pinfunction "-IN_13") (pintype "input"))
      (node (ref "R14") (pin "1") (pinfunction "1_1") (pintype "passive"))
      (node (ref "R18") (pin "2") (pinfunction "2_2") (pintype "passive"))
      (node (ref "R26") (pin "1") (pinfunction "1_1") (pintype "passive"))
    )
    (net (code "64") (name "Net-(IC7A--IN)") (class "Default")
      (node (ref "C40") (pin "1") (pinfunction "1_1") (pintype "passive"))
      (node (ref "IC7") (pin "2") (pinfunction "-IN_2") (pintype "input"))
      (node (ref "R15") (pin "1") (pinfunction "1_1") (pintype "passive"))
      (node (ref "R19") (pin "2") (pinfunction "2_2") (pintype "passive"))
      (node (ref "R23") (pin "1") (pinfunction "1_1") (pintype "passive"))
    )
    (net (code "65") (name "Net-(IC7B--IN)") (class "Default")
      (node (ref "C48") (pin "1") (pinfunction "1_1") (pintype "passive"))
      (node (ref "IC7") (pin "6") (pinfunction "-IN_6") (pintype "input"))
      (node (ref "R29") (pin "1") (pinfunction "1_1") (pintype "passive"))
      (node (ref "R34") (pin "2") (pinfunction "2_2") (pintype "passive"))
      (node (ref "R38") (pin "1") (pinfunction "1_1") (pintype "passive"))
    )
    (net (code "66") (name "Net-(IC7C--IN)") (class "Default")
      (node (ref "C49") (pin "1") (pinfunction "1_1") (pintype "passive"))
      (node (ref "IC7") (pin "9") (pinfunction "-IN_9") (pintype "input"))
      (node (ref "R35") (pin "2") (pinfunction "2_2") (pintype "passive"))
      (node (ref "R36") (pin "1") (pinfunction "1_1") (pintype "passive"))
      (node (ref "R39") (pin "1") (pinfunction "1_1") (pintype "passive"))
    )
    (net (code "67") (name "Net-(IC7D--IN)") (class "Default")
      (node (ref "C41") (pin "1") (pinfunction "1_1") (pintype "passive"))
      (node (ref "IC7") (pin "13") (pinfunction "-IN_13") (pintype "input"))
      (node (ref "R13") (pin "1") (pinfunction "1_1") (pintype "passive"))
      (node (ref "R20") (pin "2") (pinfunction "2_2") (pintype "passive"))
      (node (ref "R27") (pin "1") (pinfunction "1_1") (pintype "passive"))
    )
    (net (code "68") (name "Net-(IC8A--IN)") (class "Default")
      (node (ref "C42") (pin "1") (pinfunction "1_1") (pintype "passive"))
      (node (ref "IC8") (pin "2") (pinfunction "-IN_2") (pintype "input"))
      (node (ref "R21") (pin "1") (pinfunction "1_1") (pintype "passive"))
      (node (ref "R22") (pin "2") (pinfunction "2_2") (pintype "passive"))
    )
    (net (code "69") (name "Net-(IC8A-OUT)") (class "Default")
      (node (ref "C42") (pin "2") (pinfunction "2_2") (pintype "passive"))
      (node (ref "IC8") (pin "1") (pinfunction "OUT_1") (pintype "output"))
      (node (ref "R22") (pin "1") (pinfunction "1_1") (pintype "passive"))
      (node (ref "R46") (pin "2") (pinfunction "2_2") (pintype "passive"))
    )
    (net (code "70") (name "Net-(IC8B--IN)") (class "Default")
      (node (ref "C43") (pin "1") (pinfunction "1_1") (pintype "passive"))
      (node (ref "IC8") (pin "6") (pinfunction "-IN_6") (pintype "input"))
      (node (ref "R16") (pin "1") (pinfunction "1_1") (pintype "passive"))
      (node (ref "R28") (pin "2") (pinfunction "2_2") (pintype "passive"))
    )
    (net (code "71") (name "Net-(IC8B-OUT)") (class "Default")
      (node (ref "C43") (pin "2") (pinfunction "2_2") (pintype "passive"))
      (node (ref "IC8") (pin "7") (pinfunction "OUT_7") (pintype "output"))
      (node (ref "R28") (pin "1") (pinfunction "1_1") (pintype "passive"))
      (node (ref "R47") (pin "2") (pinfunction "2_2") (pintype "passive"))
    )
    (net (code "72") (name "Net-(J1-3)") (class "Default")
      (node (ref "C55") (pin "1") (pinfunction "1_1") (pintype "passive"))
      (node (ref "J1") (pin "P3") (pinfunction "3_P3") (pintype "passive"))
      (node (ref "R40") (pin "2") (pinfunction "2_2") (pintype "passive"))
    )
    (net (code "73") (name "Net-(J2-2)") (class "Default")
      (node (ref "J2") (pin "P2") (pinfunction "2_P2") (pintype "passive"))
      (node (ref "R48") (pin "1") (pinfunction "1_1") (pintype "passive"))
    )
    (net (code "74") (name "Net-(J2-3)") (class "Default")
      (node (ref "C56") (pin "1") (pinfunction "1_1") (pintype "passive"))
      (node (ref "J2") (pin "P3") (pinfunction "3_P3") (pintype "passive"))
      (node (ref "R41") (pin "2") (pinfunction "2_2") (pintype "passive"))
    )
    (net (code "75") (name "Net-(J3-2)") (class "Default")
      (node (ref "J3") (pin "P2") (pinfunction "2_P2") (pintype "passive"))
      (node (ref "R49") (pin "1") (pinfunction "1_1") (pintype "passive"))
    )
    (net (code "76") (name "Net-(J3-3)") (class "Default")
      (node (ref "C57") (pin "1") (pinfunction "1_1") (pintype "passive"))
      (node (ref "J3") (pin "P3") (pinfunction "3_P3") (pintype "passive"))
      (node (ref "R15") (pin "2") (pinfunction "2_2") (pintype "passive"))
    )
    (net (code "77") (name "Net-(J4-2)") (class "Default")
      (node (ref "J4") (pin "P2") (pinfunction "2_P2") (pintype "passive"))
      (node (ref "R45") (pin "1") (pinfunction "1_1") (pintype "passive"))
    )
    (net (code "78") (name "Net-(J4-3)") (class "Default")
      (node (ref "C54") (pin "1") (pinfunction "1_1") (pintype "passive"))
      (node (ref "J4") (pin "P3") (pinfunction "3_P3") (pintype "passive"))
      (node (ref "R39") (pin "2") (pinfunction "2_2") (pintype "passive"))
    )
    (net (code "79") (name "Net-(J5-3)") (class "Default")
      (node (ref "C58") (pin "1") (pinfunction "1_1") (pintype "passive"))
      (node (ref "J5") (pin "P3") (pinfunction "3_P3") (pintype "passive"))
      (node (ref "R13") (pin "2") (pinfunction "2_2") (pintype "passive"))
    )
    (net (code "80") (name "Net-(J6-2)") (class "Default")
      (node (ref "J6") (pin "P2") (pinfunction "2_P2") (pintype "passive"))
      (node (ref "R50") (pin "2") (pinfunction "2_2") (pintype "passive"))
    )
    (net (code "81") (name "Net-(J6-3)") (class "Default")
      (node (ref "C59") (pin "1") (pinfunction "1_1") (pintype "passive"))
      (node (ref "J6") (pin "P3") (pinfunction "3_P3") (pintype "passive"))
      (node (ref "R24") (pin "2") (pinfunction "2_2") (pintype "passive"))
    )
    (net (code "82") (name "Net-(J7-2)") (class "Default")
      (node (ref "J7") (pin "P2") (pinfunction "2_P2") (pintype "passive"))
      (node (ref "R51") (pin "1") (pinfunction "1_1") (pintype "passive"))
    )
    (net (code "83") (name "Net-(J7-3)") (class "Default")
      (node (ref "C61") (pin "1") (pinfunction "1_1") (pintype "passive"))
      (node (ref "J7") (pin "P3") (pinfunction "3_P3") (pintype "passive"))
      (node (ref "R14") (pin "2") (pinfunction "2_2") (pintype "passive"))
    )
    (net (code "84") (name "Net-(J8-3)") (class "Default")
      (node (ref "C60") (pin "1") (pinfunction "1_1") (pintype "passive"))
      (node (ref "J8") (pin "P3") (pinfunction "3_P3") (pintype "passive"))
      (node (ref "R38") (pin "2") (pinfunction "2_2") (pintype "passive"))
    )
    (net (code "85") (name "Net-(J9-3)") (class "Default")
      (node (ref "J9") (pin "P3") (pinfunction "3_P3") (pintype "passive"))
      (node (ref "R46") (pin "1") (pinfunction "1_1") (pintype "passive"))
    )
    (net (code "86") (name "Net-(J10-3)") (class "Default")
      (node (ref "J10") (pin "P3") (pinfunction "3_P3") (pintype "passive"))
      (node (ref "R47") (pin "1") (pinfunction "1_1") (pintype "passive"))
    )
    (net (code "87") (name "Net-(JP5-Pad1)") (class "Default")
      (node (ref "JP5") (pin "1") (pinfunction "1_1") (pintype "passive"))
      (node (ref "R9") (pin "1") (pinfunction "1_1") (pintype "passive"))
    )
    (net (code "88") (name "Net-(JP5-Pad2)") (class "Default")
      (node (ref "JP5") (pin "2") (pinfunction "2_2") (pintype "passive"))
      (node (ref "R10") (pin "1") (pinfunction "1_1") (pintype "passive"))
    )
    (net (code "89") (name "Net-(Q1B-2)") (class "Default")
      (node (ref "C14") (pin "2") (pinfunction "2_2") (pintype "passive"))
      (node (ref "Q1") (pin "3") (pinfunction "2_3") (pintype "passive"))
      (node (ref "R5") (pin "2") (pinfunction "2_2") (pintype "passive"))
    )
    (net (code "90") (name "RESET") (class "Default")
      (node (ref "C15") (pin "1") (pinfunction "1_1") (pintype "passive"))
      (node (ref "IC4") (pin "7") (pinfunction "NRST_7") (pintype "bidirectional"))
      (node (ref "JP6") (pin "4") (pinfunction "4_4") (pintype "passive"))
      (node (ref "R4") (pin "2") (pinfunction "2_2") (pintype "passive"))
    )
    (net (code "91") (name "RX") (class "Default")
      (node (ref "IC4") (pin "46") (pinfunction "PB9/SPI2_NSS/I2S2_WS/I2C1_SDA/USART3_RX/CAN_TX/TIM4_CH4_46") (pintype "bidirectional"))
      (node (ref "R9") (pin "2") (pinfunction "2_2") (pintype "passive"))
    )
    (net (code "92") (name "SWCLK") (class "Default")
      (node (ref "IC4") (pin "37") (pinfunction "PA14/I2C1_SDA/JTCK-SWCLK_37") (pintype "bidirectional"))
      (node (ref "JP6") (pin "3") (pinfunction "3_3") (pintype "passive"))
    )
    (net (code "93") (name "SWDIO") (class "Default")
      (node (ref "IC4") (pin "34") (pinfunction "PA13/SPI1_MISO/I2S1_MCK/USART3_CTS/TIM4_CH3/TIM5_CH4/JTMS-SWDIO_34") (pintype "bidirectional"))
      (node (ref "JP6") (pin "2") (pinfunction "2_2") (pintype "passive"))
    )
    (net (code "94") (name "SW_1") (class "Default")
      (node (ref "IC4") (pin "43") (pinfunction "PB7/I2C1_SDA/USART1_RX/TIM4_CH2_43") (pintype "bidirectional"))
      (node (ref "SW1") (pin "3") (pinfunction "3_3") (pintype "passive"))
      (node (ref "SW1") (pin "4") (pinfunction "4_4") (pintype "passive"))
    )
    (net (code "95") (name "SW_2") (class "Default")
      (node (ref "IC4") (pin "42") (pinfunction "PB6/I2C1_SCL/USART1_TX/TIM4_CH1_42") (pintype "bidirectional"))
      (node (ref "SW2") (pin "3") (pinfunction "3_3") (pintype "passive"))
      (node (ref "SW2") (pin "4") (pinfunction "4_4") (pintype "passive"))
    )
    (net (code "96") (name "TIMBRE_ATT") (class "Default")
      (node (ref "C53") (pin "1") (pinfunction "1_1") (pintype "passive"))
      (node (ref "IC4") (pin "16") (pinfunction "PA6/SPI1_MISO/I2S1_MCK/TIM3_CH1/ADC_IN6/DAC2_OUT1_16") (pintype "bidirectional"))
      (node (ref "R42") (pin "P$2") (pinfunction "S_P$2") (pintype "passive"))
    )
    (net (code "97") (name "TIMBRE_POT") (class "Default")
      (node (ref "C32") (pin "1") (pinfunction "1_1") (pintype "passive"))
      (node (ref "IC4") (pin "13") (pinfunction "PA3/SPI3_MOSI/I2S3_SD/USART2_RX/TIM2_CH4/TIM5_CH4/ADC_IN3_13") (pintype "bidirectional"))
      (node (ref "R7") (pin "P$2") (pinfunction "S_P$2") (pintype "passive"))
    )
    (net (code "98") (name "TX") (class "Default")
      (node (ref "IC4") (pin "45") (pinfunction "PB8/SPI2_SCK/I2S2_CK/I2C1_SCL/USART3_TX/CAN_RX/TIM4_CH3_45") (pintype "bidirectional"))
      (node (ref "R10") (pin "2") (pinfunction "2_2") (pintype "passive"))
    )
    (net (code "99") (name "VCC") (class "Default")
      (node (ref "C37") (pin "1") (pinfunction "1_1") (pintype "passive"))
      (node (ref "C4") (pin "+") (pinfunction "+_+") (pintype "passive"))
      (node (ref "IC8") (pin "8") (pinfunction "V+_8") (pintype "power_in"))
      (node (ref "L2") (pin "1") (pinfunction "1_1") (pintype "passive"))
    )
    (net (code "100") (name "VEE") (class "Default")
      (node (ref "C45") (pin "2") (pinfunction "2_2") (pintype "passive"))
      (node (ref "C5") (pin "-") (pinfunction "-_-") (pintype "passive"))
      (node (ref "IC8") (pin "4") (pinfunction "V-_4") (pintype "power_in"))
      (node (ref "L3") (pin "1") (pinfunction "1_1") (pintype "passive"))
      (node (ref "R37") (pin "1") (pinfunction "1_1") (pintype "passive"))
    )
    (net (code "101") (name "unconnected-(IC2-SOUT-Pad22)") (class "Default")
      (node (ref "IC2") (pin "22") (pinfunction "SOUT_22") (pintype "bidirectional"))
    )
    (net (code "102") (name "unconnected-(IC4-PA15{slash}SPI1_NSS{slash}I2S1_WS{slash}SPI3_NSS{slash}I2S3_WS{slash}I2C1_SCL{slash}TIM2_CH1_ETR{slash}JTDI-Pad38)") (class "Default")
      (node (ref "IC4") (pin "38") (pinfunction "PA15/SPI1_NSS/I2S1_WS/SPI3_NSS/I2S3_WS/I2C1_SCL/TIM2_CH1_ETR/JTDI_38") (pintype "bidirectional"))
    )
    (net (code "103") (name "unconnected-(IC4-PB3{slash}SPI1_SCK{slash}I2S1_CK{slash}SPI3_SCK{slash}I2S3_CK{slash}USART2_TX{slash}TIM2_CH2{slash}JTDO{slash}SPI3_SCK{slash}JTDO-Pad39)") (class "Default")
      (node (ref "IC4") (pin "39") (pinfunction "PB3/SPI1_SCK/I2S1_CK/SPI3_SCK/I2S3_CK/USART2_TX/TIM2_CH2/JTDO/SPI3_SCK/JTDO_39") (pintype "bidirectional"))
    )
    (net (code "104") (name "unconnected-(IC4-PB4{slash}SPI1_MISO{slash}I2S1_MCK{slash}SPI3_MISO{slash}I2S3_MCK{slash}USART2_RX{slash}TIM3_CH1{slash}NJTRST-Pad40)") (class "Default")
      (node (ref "IC4") (pin "40") (pinfunction "PB4/SPI1_MISO/I2S1_MCK/SPI3_MISO/I2S3_MCK/USART2_RX/TIM3_CH1/NJTRST_40") (pintype "bidirectional"))
    )
    (net (code "105") (name "unconnected-(IC4-PB5{slash}SPI1_MOSI{slash}I2S1_SD{slash}SPI3_MOSI{slash}I2S3_SD{slash}I2C1_SMBAI{slash}USART2_CK{slash}TIM3_CH2-Pad41)") (class "Default")
      (node (ref "IC4") (pin "41") (pinfunction "PB5/SPI1_MOSI/I2S1_SD/SPI3_MOSI/I2S3_SD/I2C1_SMBAI/USART2_CK/TIM3_CH2_41") (pintype "bidirectional"))
    )
    (net (code "106") (name "unconnected-(IC4-PC13{slash}TIMESTAMP{slash}RTC_TAMPER1-Pad2)") (class "Default")
      (node (ref "IC4") (pin "2") (pinfunction "PC13/TIMESTAMP/RTC_TAMPER1_2") (pintype "bidirectional"))
    )
    (net (code "107") (name "unconnected-(IC4-PC14{slash}OSC32_IN-Pad3)") (class "Default")
      (node (ref "IC4") (pin "3") (pinfunction "PC14/OSC32_IN_3") (pintype "bidirectional"))
    )
    (net (code "108") (name "unconnected-(IC4-PC15{slash}OSC32_OUT-Pad4)") (class "Default")
      (node (ref "IC4") (pin "4") (pinfunction "PC15/OSC32_OUT_4") (pintype "bidirectional"))
    )
    (net (code "109") (name "unconnected-(J9-2-PadP2)") (class "Default")
      (node (ref "J9") (pin "P2") (pinfunction "2_P2") (pintype "passive"))
    )
    (net (code "110") (name "unconnected-(J10-2-PadP2)") (class "Default")
      (node (ref "J10") (pin "P2") (pinfunction "2_P2") (pintype "passive"))
    )
  )
)
